# swift-nav.net
KiCad netlist of a schematic drawn in EAGLE
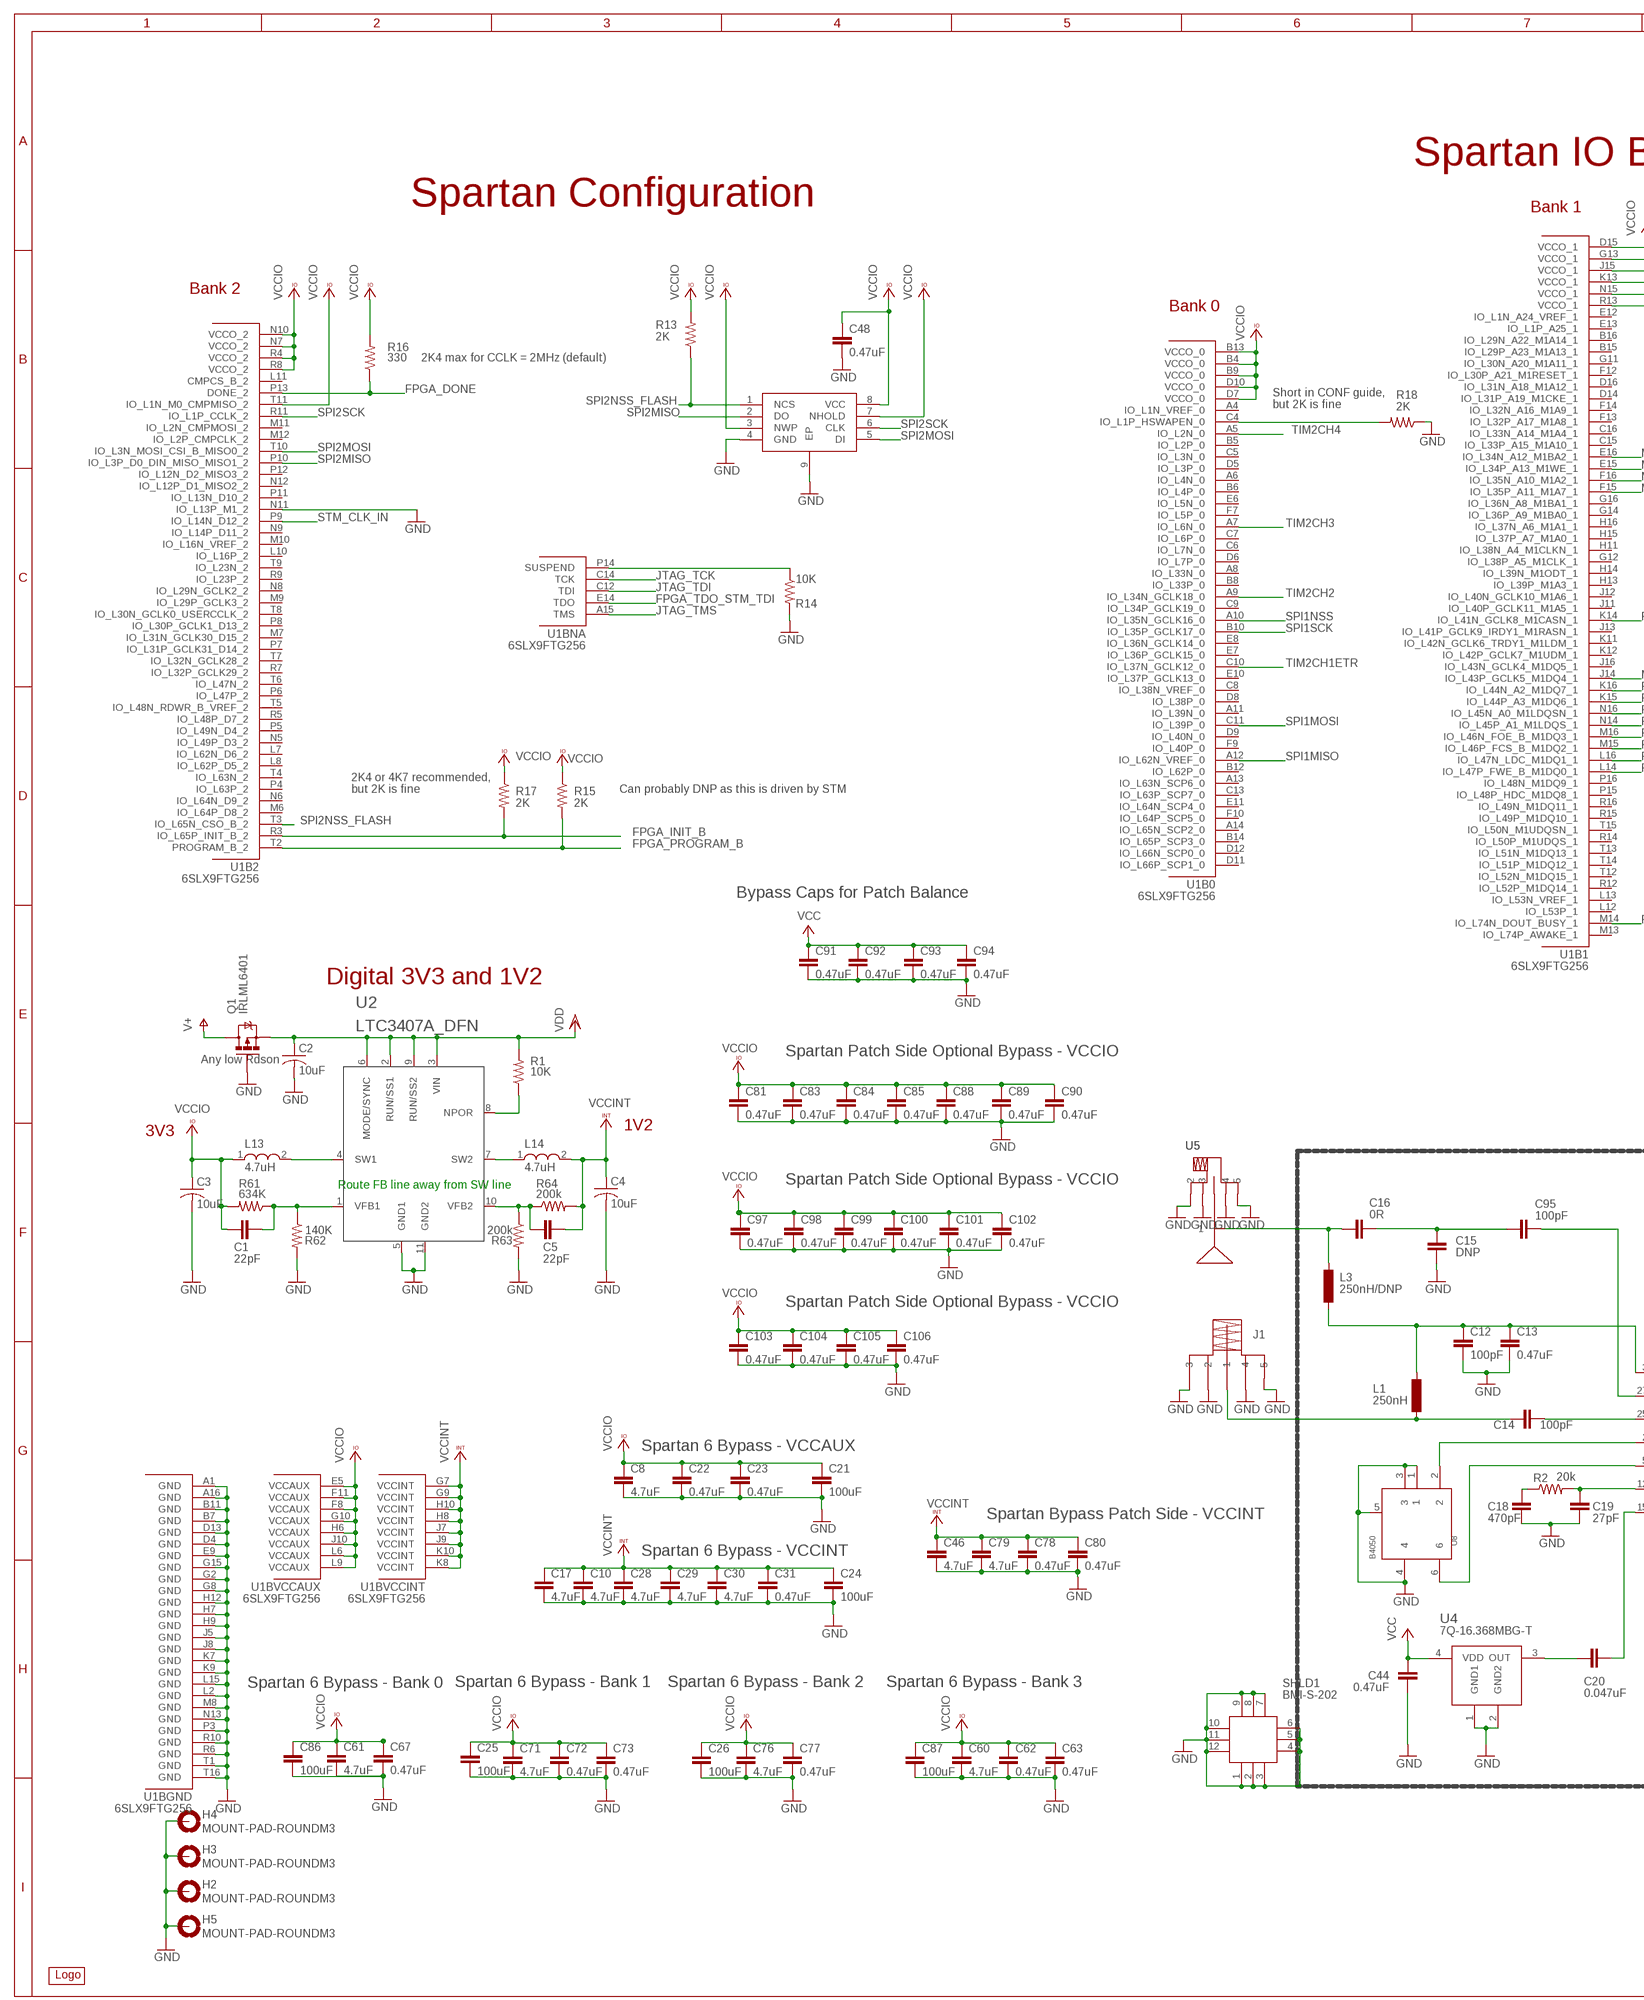
[diagram p0: schematic, sheet 1, part 1 of 2]
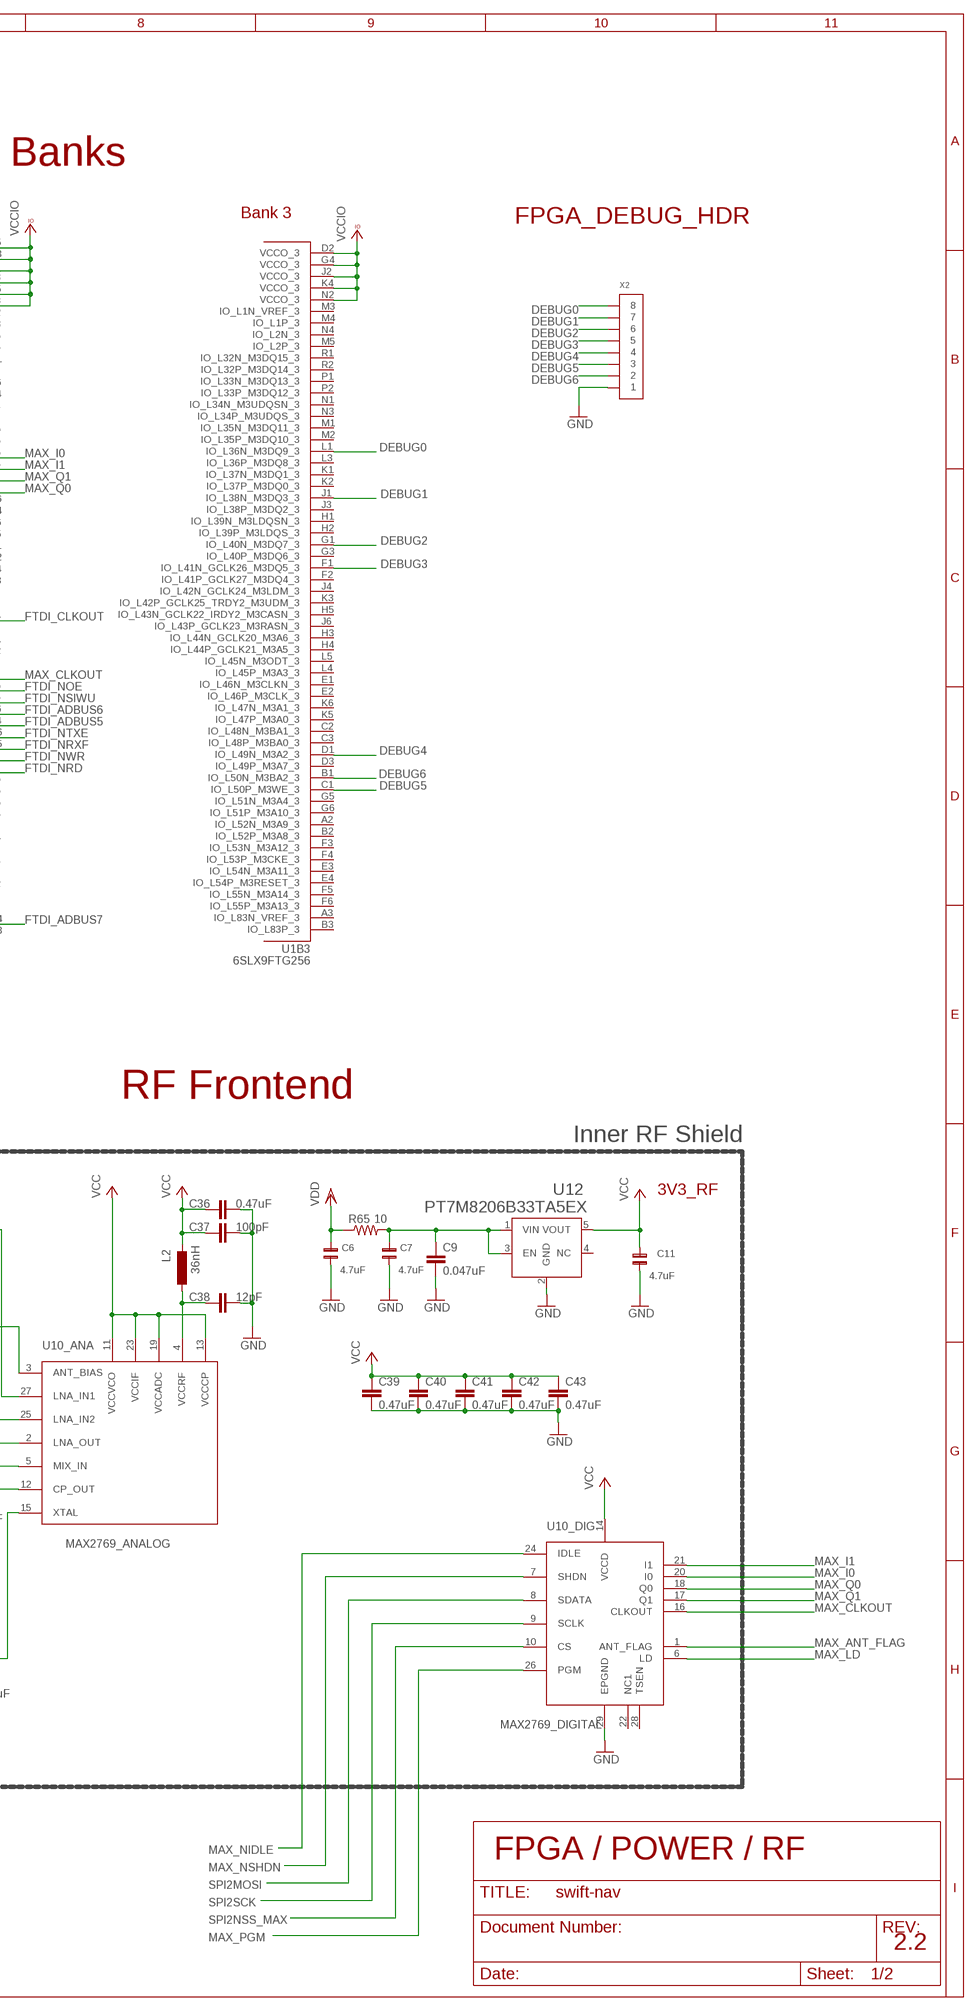
[diagram p1: schematic, sheet 1, part 2 of 2]
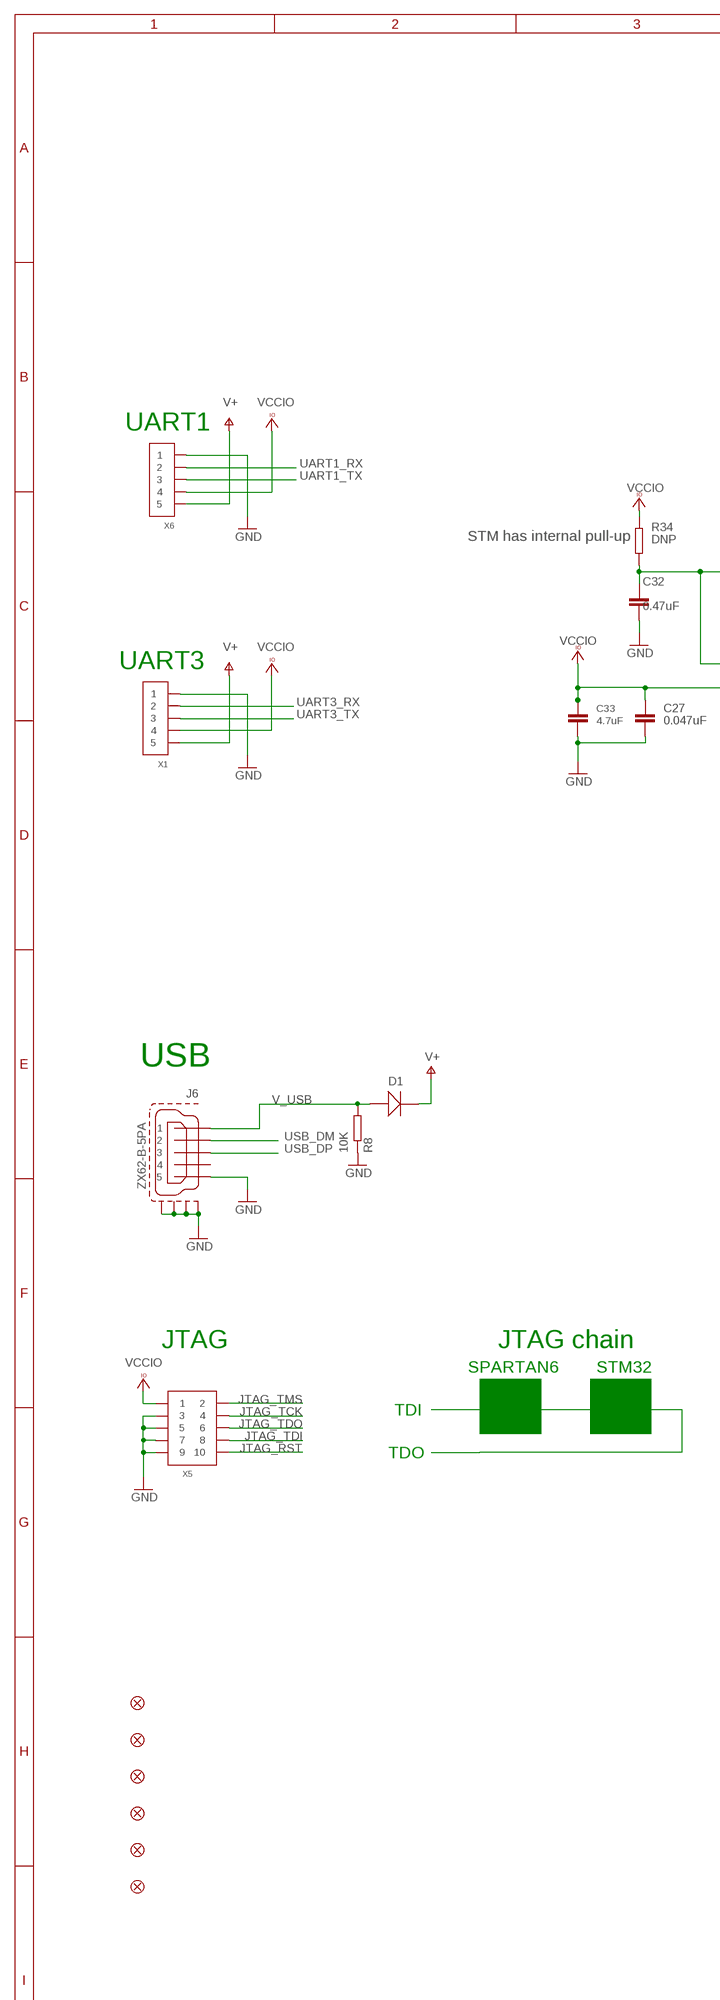
[diagram p2: schematic, sheet 2, part 1 of 2]
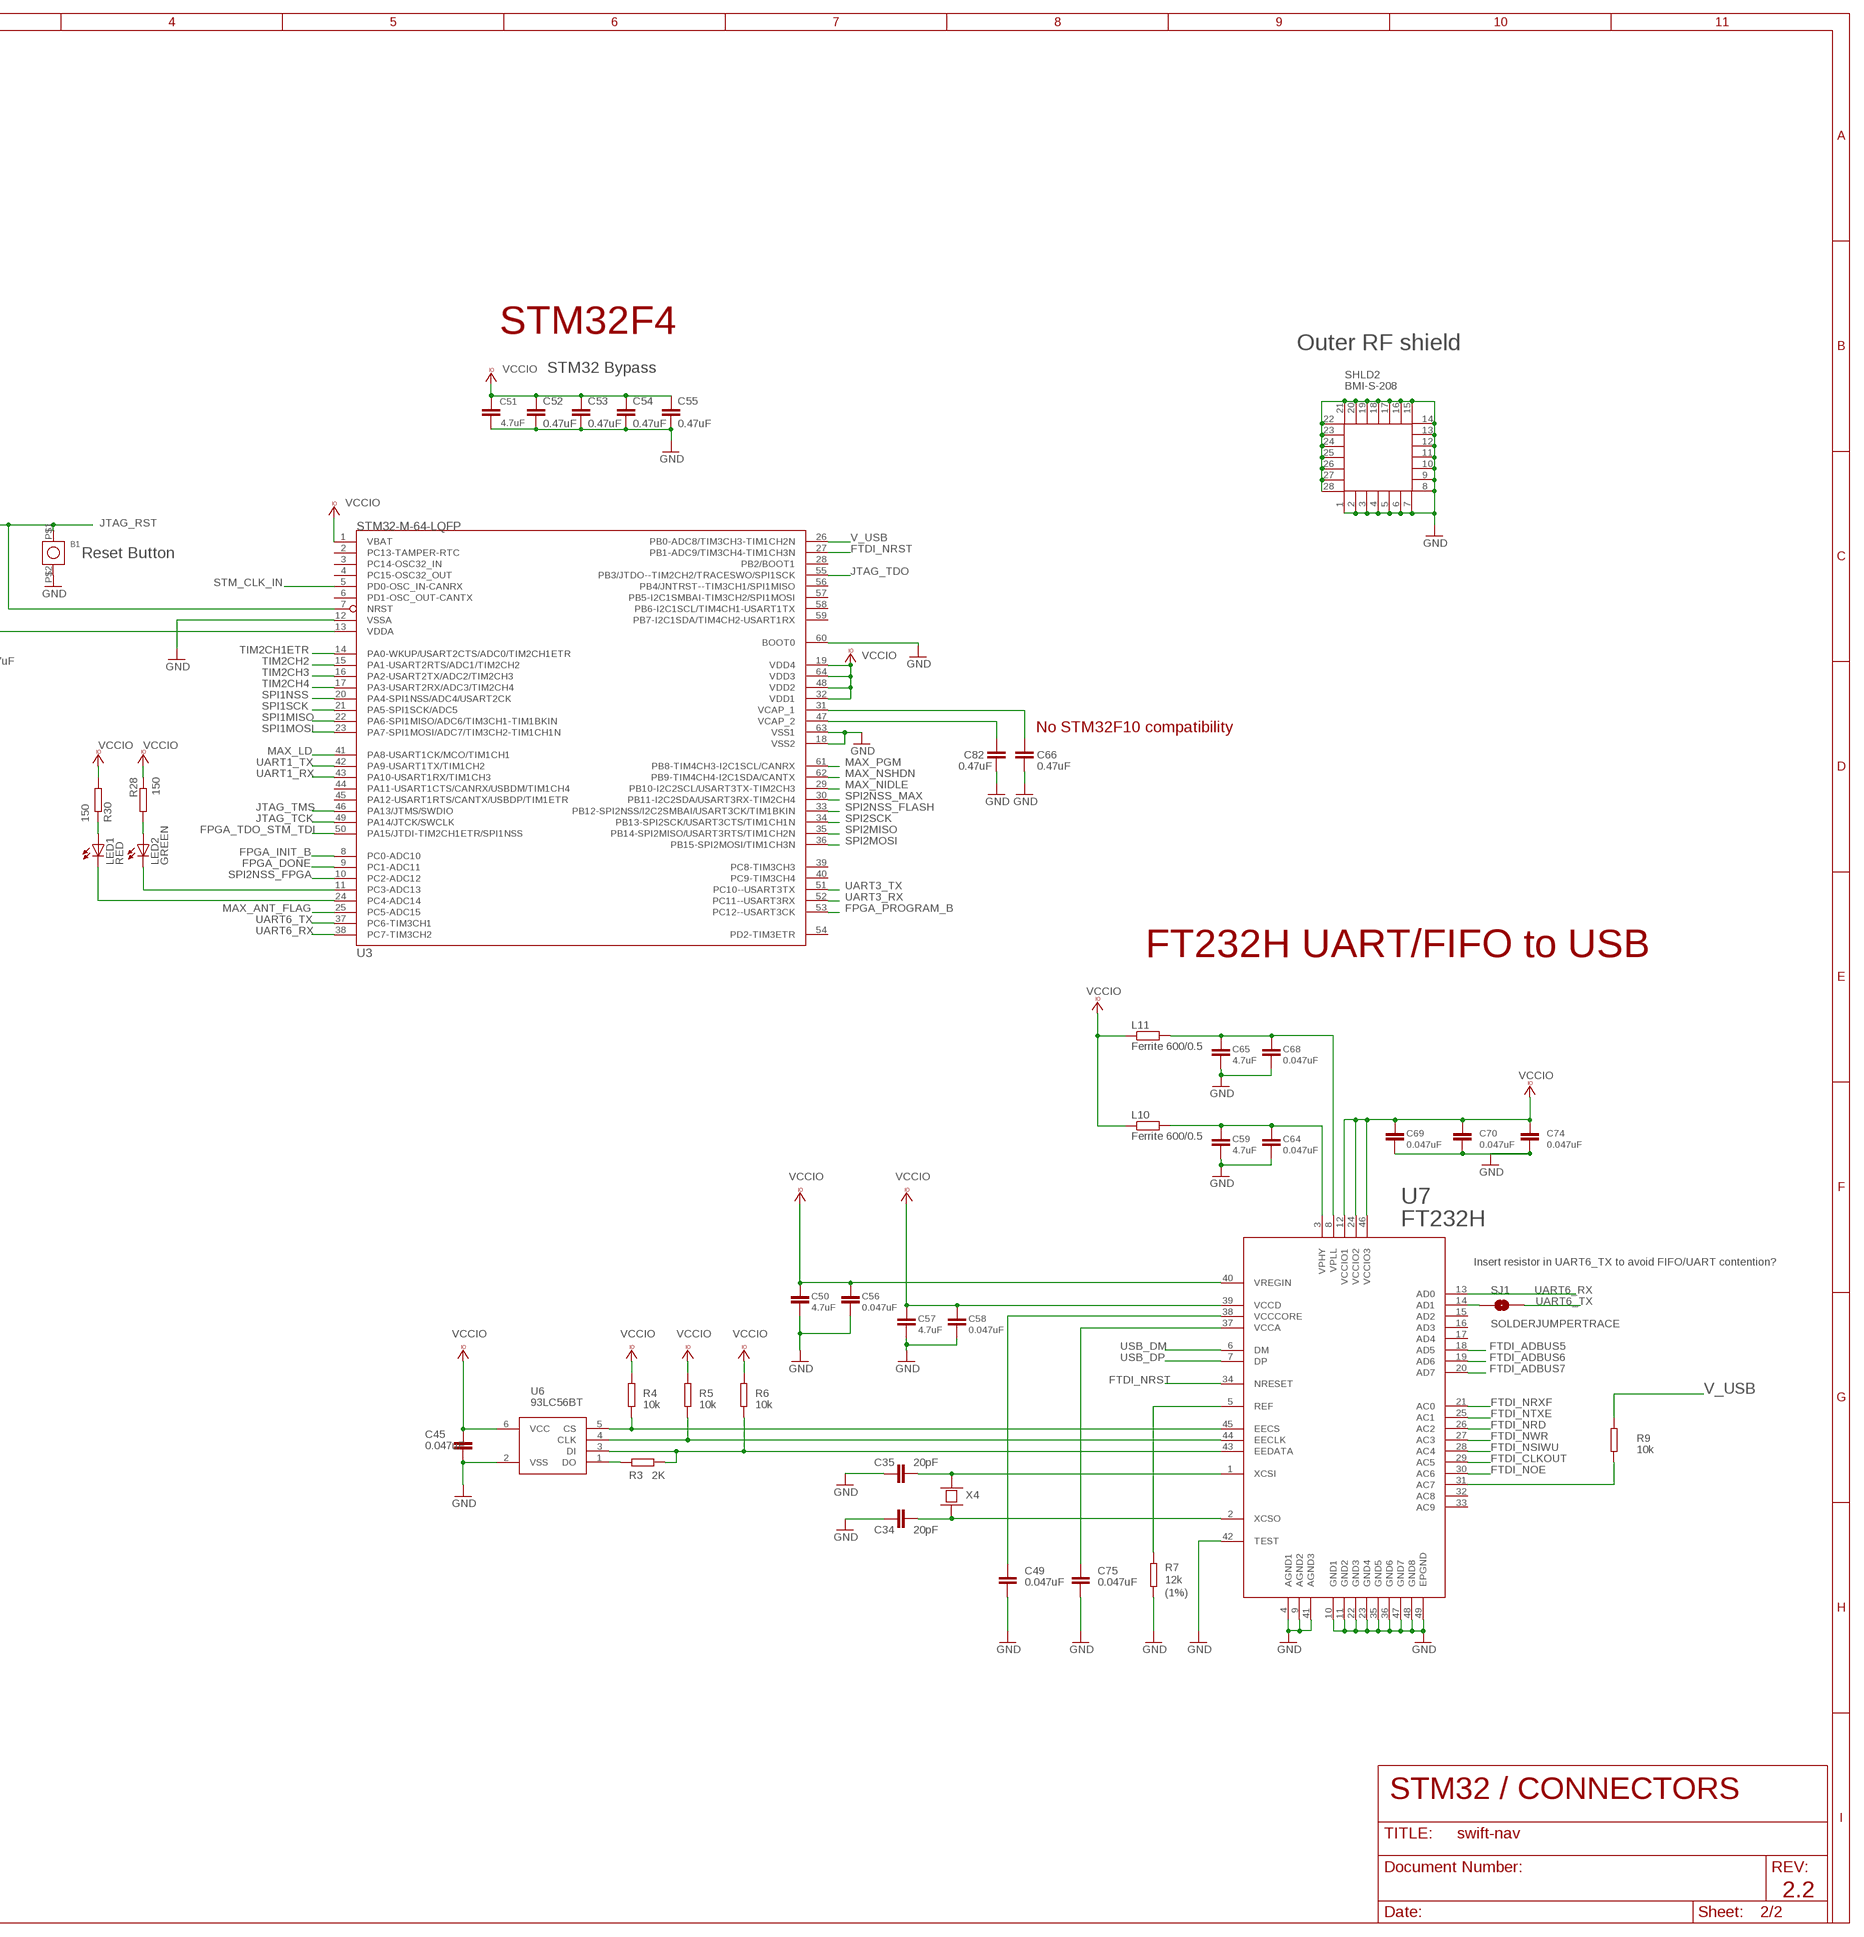
[diagram p3: schematic, sheet 2, part 2 of 2]

(export (version "E")
  (design (tool "Eeschema 10.0.6"))
  (components
    (comp (ref "C1")
      (value "22pF")
      (footprint "eagle-import:C0402")
      (libsource (lib "eagle-import") (part "C-EUC0402"))
    )
    (comp (ref "C2")
      (value "10uF")
      (footprint "eagle-import:C1206")
      (libsource (lib "eagle-import") (part "C-USC1206"))
    )
    (comp (ref "C3")
      (value "10uF")
      (footprint "eagle-import:C1206")
      (libsource (lib "eagle-import") (part "C-USC1206"))
    )
    (comp (ref "C4")
      (value "10uF")
      (footprint "eagle-import:C1206")
      (libsource (lib "eagle-import") (part "C-USC1206"))
    )
    (comp (ref "C5")
      (value "22pF")
      (footprint "eagle-import:C0402")
      (libsource (lib "eagle-import") (part "C-EUC0402"))
    )
    (comp (ref "C6")
      (value "4.7uF")
      (footprint "eagle-import:0603")
      (libsource (lib "eagle-import") (part "C0603"))
    )
    (comp (ref "C7")
      (value "4.7uF")
      (footprint "eagle-import:0603")
      (libsource (lib "eagle-import") (part "C0603"))
    )
    (comp (ref "C8")
      (value "4.7uF")
      (footprint "eagle-import:C0603K")
      (libsource (lib "eagle-import") (part "C-EUC0603K"))
    )
    (comp (ref "C9")
      (value "0.047uF")
      (footprint "eagle-import:C0402")
      (libsource (lib "eagle-import") (part "C-EUC0402"))
    )
    (comp (ref "C10")
      (value "4.7uF")
      (footprint "eagle-import:C0603K")
      (libsource (lib "eagle-import") (part "C-EUC0603K"))
    )
    (comp (ref "C11")
      (value "4.7uF")
      (footprint "eagle-import:0603")
      (libsource (lib "eagle-import") (part "C0603"))
    )
    (comp (ref "C12")
      (value "100pF")
      (footprint "eagle-import:C0402")
      (libsource (lib "eagle-import") (part "C-EUC0402"))
    )
    (comp (ref "C13")
      (value "0.47uF")
      (footprint "eagle-import:C0402")
      (libsource (lib "eagle-import") (part "C-EUC0402"))
    )
    (comp (ref "C14")
      (value "100pF")
      (footprint "eagle-import:C0402")
      (libsource (lib "eagle-import") (part "C-EUC0402"))
    )
    (comp (ref "C15")
      (value "DNP")
      (footprint "eagle-import:C0402")
      (libsource (lib "eagle-import") (part "C-EUC0402"))
    )
    (comp (ref "C16")
      (value "0R")
      (footprint "eagle-import:C0402")
      (libsource (lib "eagle-import") (part "C-EUC0402"))
    )
    (comp (ref "C17")
      (value "4.7uF")
      (footprint "eagle-import:C0603K")
      (libsource (lib "eagle-import") (part "C-EUC0603K"))
    )
    (comp (ref "C18")
      (value "470pF")
      (footprint "eagle-import:C0402")
      (libsource (lib "eagle-import") (part "C-EUC0402"))
    )
    (comp (ref "C19")
      (value "27pF")
      (footprint "eagle-import:C0402")
      (libsource (lib "eagle-import") (part "C-EUC0402"))
    )
    (comp (ref "C20")
      (value "0.047uF")
      (footprint "eagle-import:C0402")
      (libsource (lib "eagle-import") (part "C-EUC0402"))
    )
    (comp (ref "C21")
      (value "100uF")
      (footprint "eagle-import:C1210K")
      (libsource (lib "eagle-import") (part "C-EUC1210K"))
    )
    (comp (ref "C22")
      (value "0.47uF")
      (footprint "eagle-import:C0402")
      (libsource (lib "eagle-import") (part "C-EUC0402"))
    )
    (comp (ref "C23")
      (value "0.47uF")
      (footprint "eagle-import:C0402")
      (libsource (lib "eagle-import") (part "C-EUC0402"))
    )
    (comp (ref "C24")
      (value "100uF")
      (footprint "eagle-import:C1210K")
      (libsource (lib "eagle-import") (part "C-EUC1210K"))
    )
    (comp (ref "C25")
      (value "100uF")
      (footprint "eagle-import:C1210K")
      (libsource (lib "eagle-import") (part "C-EUC1210K"))
    )
    (comp (ref "C26")
      (value "100uF")
      (footprint "eagle-import:C1210K")
      (libsource (lib "eagle-import") (part "C-EUC1210K"))
    )
    (comp (ref "C28")
      (value "4.7uF")
      (footprint "eagle-import:C0603K")
      (libsource (lib "eagle-import") (part "C-EUC0603K"))
    )
    (comp (ref "C29")
      (value "4.7uF")
      (footprint "eagle-import:C0603K")
      (libsource (lib "eagle-import") (part "C-EUC0603K"))
    )
    (comp (ref "C30")
      (value "4.7uF")
      (footprint "eagle-import:C0603K")
      (libsource (lib "eagle-import") (part "C-EUC0603K"))
    )
    (comp (ref "C31")
      (value "0.47uF")
      (footprint "eagle-import:C0402")
      (libsource (lib "eagle-import") (part "C-EUC0402"))
    )
    (comp (ref "C36")
      (value "0.47uF")
      (footprint "eagle-import:C0402")
      (libsource (lib "eagle-import") (part "C-EUC0402"))
    )
    (comp (ref "C37")
      (value "100pF")
      (footprint "eagle-import:C0402")
      (libsource (lib "eagle-import") (part "C-EUC0402"))
    )
    (comp (ref "C38")
      (value "12pF")
      (footprint "eagle-import:C0402")
      (libsource (lib "eagle-import") (part "C-EUC0402"))
    )
    (comp (ref "C39")
      (value "0.47uF")
      (footprint "eagle-import:C0402")
      (libsource (lib "eagle-import") (part "C-EUC0402"))
    )
    (comp (ref "C40")
      (value "0.47uF")
      (footprint "eagle-import:C0402")
      (libsource (lib "eagle-import") (part "C-EUC0402"))
    )
    (comp (ref "C41")
      (value "0.47uF")
      (footprint "eagle-import:C0402")
      (libsource (lib "eagle-import") (part "C-EUC0402"))
    )
    (comp (ref "C42")
      (value "0.47uF")
      (footprint "eagle-import:C0402")
      (libsource (lib "eagle-import") (part "C-EUC0402"))
    )
    (comp (ref "C43")
      (value "0.47uF")
      (footprint "eagle-import:C0402")
      (libsource (lib "eagle-import") (part "C-EUC0402"))
    )
    (comp (ref "C44")
      (value "0.47uF")
      (footprint "eagle-import:C0402")
      (libsource (lib "eagle-import") (part "C-EUC0402"))
    )
    (comp (ref "C46")
      (value "4.7uF")
      (footprint "eagle-import:C0603K")
      (libsource (lib "eagle-import") (part "C-EUC0603K"))
    )
    (comp (ref "C48")
      (value "0.47uF")
      (footprint "eagle-import:C0402")
      (libsource (lib "eagle-import") (part "C-EUC0402"))
    )
    (comp (ref "C60")
      (value "4.7uF")
      (footprint "eagle-import:C0603K")
      (libsource (lib "eagle-import") (part "C-EUC0603K"))
    )
    (comp (ref "C61")
      (value "4.7uF")
      (footprint "eagle-import:C0603K")
      (libsource (lib "eagle-import") (part "C-EUC0603K"))
    )
    (comp (ref "C62")
      (value "0.47uF")
      (footprint "eagle-import:C0402")
      (libsource (lib "eagle-import") (part "C-EUC0402"))
    )
    (comp (ref "C63")
      (value "0.47uF")
      (footprint "eagle-import:C0402")
      (libsource (lib "eagle-import") (part "C-EUC0402"))
    )
    (comp (ref "C67")
      (value "0.47uF")
      (footprint "eagle-import:C0402")
      (libsource (lib "eagle-import") (part "C-EUC0402"))
    )
    (comp (ref "C71")
      (value "4.7uF")
      (footprint "eagle-import:C0603K")
      (libsource (lib "eagle-import") (part "C-EUC0603K"))
    )
    (comp (ref "C72")
      (value "0.47uF")
      (footprint "eagle-import:C0402")
      (libsource (lib "eagle-import") (part "C-EUC0402"))
    )
    (comp (ref "C73")
      (value "0.47uF")
      (footprint "eagle-import:C0402")
      (libsource (lib "eagle-import") (part "C-EUC0402"))
    )
    (comp (ref "C76")
      (value "4.7uF")
      (footprint "eagle-import:C0603K")
      (libsource (lib "eagle-import") (part "C-EUC0603K"))
    )
    (comp (ref "C77")
      (value "0.47uF")
      (footprint "eagle-import:C0402")
      (libsource (lib "eagle-import") (part "C-EUC0402"))
    )
    (comp (ref "C78")
      (value "0.47uF")
      (footprint "eagle-import:C0402")
      (libsource (lib "eagle-import") (part "C-EUC0402"))
    )
    (comp (ref "C79")
      (value "4.7uF")
      (footprint "eagle-import:C0603K")
      (libsource (lib "eagle-import") (part "C-EUC0603K"))
    )
    (comp (ref "C80")
      (value "0.47uF")
      (footprint "eagle-import:C0402")
      (libsource (lib "eagle-import") (part "C-EUC0402"))
    )
    (comp (ref "C81")
      (value "0.47uF")
      (footprint "eagle-import:C0402")
      (libsource (lib "eagle-import") (part "C-EUC0402"))
    )
    (comp (ref "C83")
      (value "0.47uF")
      (footprint "eagle-import:C0402")
      (libsource (lib "eagle-import") (part "C-EUC0402"))
    )
    (comp (ref "C84")
      (value "0.47uF")
      (footprint "eagle-import:C0402")
      (libsource (lib "eagle-import") (part "C-EUC0402"))
    )
    (comp (ref "C85")
      (value "0.47uF")
      (footprint "eagle-import:C0402")
      (libsource (lib "eagle-import") (part "C-EUC0402"))
    )
    (comp (ref "C86")
      (value "100uF")
      (footprint "eagle-import:C1210K")
      (libsource (lib "eagle-import") (part "C-EUC1210K"))
    )
    (comp (ref "C87")
      (value "100uF")
      (footprint "eagle-import:C1210K")
      (libsource (lib "eagle-import") (part "C-EUC1210K"))
    )
    (comp (ref "C88")
      (value "0.47uF")
      (footprint "eagle-import:C0402")
      (libsource (lib "eagle-import") (part "C-EUC0402"))
    )
    (comp (ref "C89")
      (value "0.47uF")
      (footprint "eagle-import:C0402")
      (libsource (lib "eagle-import") (part "C-EUC0402"))
    )
    (comp (ref "C90")
      (value "0.47uF")
      (footprint "eagle-import:C0402")
      (libsource (lib "eagle-import") (part "C-EUC0402"))
    )
    (comp (ref "C91")
      (value "0.47uF")
      (footprint "eagle-import:C0402")
      (libsource (lib "eagle-import") (part "C-EUC0402"))
    )
    (comp (ref "C92")
      (value "0.47uF")
      (footprint "eagle-import:C0402")
      (libsource (lib "eagle-import") (part "C-EUC0402"))
    )
    (comp (ref "C93")
      (value "0.47uF")
      (footprint "eagle-import:C0402")
      (libsource (lib "eagle-import") (part "C-EUC0402"))
    )
    (comp (ref "C94")
      (value "0.47uF")
      (footprint "eagle-import:C0402")
      (libsource (lib "eagle-import") (part "C-EUC0402"))
    )
    (comp (ref "C95")
      (value "100pF")
      (footprint "eagle-import:C0402")
      (libsource (lib "eagle-import") (part "C-EUC0402"))
    )
    (comp (ref "C97")
      (value "0.47uF")
      (footprint "eagle-import:C0402")
      (libsource (lib "eagle-import") (part "C-EUC0402"))
    )
    (comp (ref "C98")
      (value "0.47uF")
      (footprint "eagle-import:C0402")
      (libsource (lib "eagle-import") (part "C-EUC0402"))
    )
    (comp (ref "C99")
      (value "0.47uF")
      (footprint "eagle-import:C0402")
      (libsource (lib "eagle-import") (part "C-EUC0402"))
    )
    (comp (ref "C100")
      (value "0.47uF")
      (footprint "eagle-import:C0402")
      (libsource (lib "eagle-import") (part "C-EUC0402"))
    )
    (comp (ref "C101")
      (value "0.47uF")
      (footprint "eagle-import:C0402")
      (libsource (lib "eagle-import") (part "C-EUC0402"))
    )
    (comp (ref "C102")
      (value "0.47uF")
      (footprint "eagle-import:C0402")
      (libsource (lib "eagle-import") (part "C-EUC0402"))
    )
    (comp (ref "C103")
      (value "0.47uF")
      (footprint "eagle-import:C0402")
      (libsource (lib "eagle-import") (part "C-EUC0402"))
    )
    (comp (ref "C104")
      (value "0.47uF")
      (footprint "eagle-import:C0402")
      (libsource (lib "eagle-import") (part "C-EUC0402"))
    )
    (comp (ref "C105")
      (value "0.47uF")
      (footprint "eagle-import:C0402")
      (libsource (lib "eagle-import") (part "C-EUC0402"))
    )
    (comp (ref "C106")
      (value "0.47uF")
      (footprint "eagle-import:C0402")
      (libsource (lib "eagle-import") (part "C-EUC0402"))
    )
    (comp (ref "H2")
      (value "MOUNT-PAD-ROUNDM3")
      (footprint "eagle-import:M3-PAD")
      (libsource (lib "eagle-import") (part "MOUNT-PAD-ROUNDM3"))
    )
    (comp (ref "H3")
      (value "MOUNT-PAD-ROUNDM3")
      (footprint "eagle-import:M3-PAD")
      (libsource (lib "eagle-import") (part "MOUNT-PAD-ROUNDM3"))
    )
    (comp (ref "H4")
      (value "MOUNT-PAD-ROUNDM3")
      (footprint "eagle-import:M3-PAD")
      (libsource (lib "eagle-import") (part "MOUNT-PAD-ROUNDM3"))
    )
    (comp (ref "H5")
      (value "MOUNT-PAD-ROUNDM3")
      (footprint "eagle-import:M3-PAD")
      (libsource (lib "eagle-import") (part "MOUNT-PAD-ROUNDM3"))
    )
    (comp (ref "J1")
      (value "SMA_EDGE")
      (footprint "eagle-import:SMA_EDGE")
      (libsource (lib "eagle-import") (part "SMA_EDGE"))
    )
    (comp (ref "L1")
      (value "250nH")
      (footprint "eagle-import:0402-IND")
      (libsource (lib "eagle-import") (part "INDUCTOR-0402"))
    )
    (comp (ref "L2")
      (value "36nH")
      (footprint "eagle-import:0402-IND")
      (libsource (lib "eagle-import") (part "INDUCTOR-0402"))
    )
    (comp (ref "L3")
      (value "250nH/DNP")
      (footprint "eagle-import:0402-IND")
      (libsource (lib "eagle-import") (part "INDUCTOR-0402"))
    )
    (comp (ref "L13")
      (value "4.7uH")
      (footprint "eagle-import:LQM2HPN4R7MG0L")
      (libsource (lib "eagle-import") (part "LQM2HPN4R7MG0L"))
    )
    (comp (ref "L14")
      (value "4.7uH")
      (footprint "eagle-import:LQM2HPN4R7MG0L")
      (libsource (lib "eagle-import") (part "LQM2HPN4R7MG0L"))
    )
    (comp (ref "Q1")
      (value "IRLML6401")
      (footprint "eagle-import:SOT23-3")
      (libsource (lib "eagle-import") (part "MOSFET-PCHANNELSMD"))
    )
    (comp (ref "R1")
      (value "10K")
      (footprint "eagle-import:R0402")
      (libsource (lib "eagle-import") (part "R-US_R0402"))
    )
    (comp (ref "R2")
      (value "20k")
      (footprint "eagle-import:R0402")
      (libsource (lib "eagle-import") (part "R-US_R0402"))
    )
    (comp (ref "R13")
      (value "2K")
      (footprint "eagle-import:R0402")
      (libsource (lib "eagle-import") (part "R-US_R0402"))
    )
    (comp (ref "R14")
      (value "10K")
      (footprint "eagle-import:R0402")
      (libsource (lib "eagle-import") (part "R-US_R0402"))
    )
    (comp (ref "R15")
      (value "2K")
      (footprint "eagle-import:R0402")
      (libsource (lib "eagle-import") (part "R-US_R0402"))
    )
    (comp (ref "R16")
      (value "330")
      (footprint "eagle-import:R0402")
      (libsource (lib "eagle-import") (part "R-US_R0402"))
    )
    (comp (ref "R17")
      (value "2K")
      (footprint "eagle-import:R0402")
      (libsource (lib "eagle-import") (part "R-US_R0402"))
    )
    (comp (ref "R18")
      (value "2K")
      (footprint "eagle-import:R0402")
      (libsource (lib "eagle-import") (part "R-US_R0402"))
    )
    (comp (ref "R61")
      (value "634K")
      (footprint "eagle-import:R0402")
      (libsource (lib "eagle-import") (part "R-US_R0402"))
    )
    (comp (ref "R62")
      (value "140K")
      (footprint "eagle-import:R0402")
      (libsource (lib "eagle-import") (part "R-US_R0402"))
    )
    (comp (ref "R63")
      (value "200k")
      (footprint "eagle-import:R0402")
      (libsource (lib "eagle-import") (part "R-US_R0402"))
    )
    (comp (ref "R64")
      (value "200k")
      (footprint "eagle-import:R0402")
      (libsource (lib "eagle-import") (part "R-US_R0402"))
    )
    (comp (ref "R65")
      (value "10")
      (footprint "eagle-import:R0402")
      (libsource (lib "eagle-import") (part "R-US_R0402"))
    )
    (comp (ref "SHLD1")
      (value "BMI-S-202")
      (footprint "eagle-import:BMI-S-202")
      (libsource (lib "eagle-import") (part "BMI-S-202"))
    )
    (comp (ref "U$1")
      (value "LOGOINITIALS")
      (footprint "eagle-import:INITIALS")
      (libsource (lib "eagle-import") (part "LOGOINITIALS"))
    )
    (comp (ref "U1")
      (value "6SLX9FTG256")
      (footprint "eagle-import:FT256")
      (libsource (lib "eagle-import") (part "6SLX9FTG256"))
    )
    (comp (ref "U2")
      (value "LTC3407A_DFN")
      (footprint "eagle-import:DFN10")
      (libsource (lib "eagle-import") (part "LTC3407A_DFN"))
    )
    (comp (ref "U4")
      (value "7Q-16.368MBG-T")
      (footprint "eagle-import:TCX_7Q")
      (libsource (lib "eagle-import") (part "7Q-16.368MBG-T"))
    )
    (comp (ref "U5")
      (value "SMA_PATCH")
      (footprint "eagle-import:SMA_PATCH")
      (libsource (lib "eagle-import") (part "SMA_PATCH"))
    )
    (comp (ref "U8")
      (value "B4050")
      (footprint "eagle-import:B4050")
      (libsource (lib "eagle-import") (part "B4050"))
    )
    (comp (ref "U10")
      (value "MAX2769")
      (footprint "eagle-import:MAX2769")
      (libsource (lib "eagle-import") (part "MAX2769"))
    )
    (comp (ref "U12")
      (value "PT7M8206B33TA5EX")
      (footprint "eagle-import:PT7M8206B33TA5EX")
      (libsource (lib "eagle-import") (part "PT7M8206B33TA5EX"))
    )
    (comp (ref "U13")
      (value "M25PX80")
      (footprint "eagle-import:M25P80_MLP8")
      (libsource (lib "eagle-import") (part "M25P80_MLP8"))
    )
    (comp (ref "X2")
      (value "CONN_8-1-53261")
      (footprint "eagle-import:PB-53261-08")
      (libsource (lib "eagle-import") (part "CONN_8-1-53261"))
    )
    (comp (ref "B1")
      (value "B3U-1000P")
      (footprint "eagle-import:B3U-1000P")
      (libsource (lib "eagle-import") (part "B3U-1000P"))
    )
    (comp (ref "C27")
      (value "0.047uF")
      (footprint "eagle-import:C0402")
      (libsource (lib "eagle-import") (part "C-EUC0402"))
    )
    (comp (ref "C32")
      (value "0.47uF")
      (footprint "eagle-import:C0402")
      (libsource (lib "eagle-import") (part "C-EUC0402"))
    )
    (comp (ref "C33")
      (value "4.7uF")
      (footprint "eagle-import:C0603K")
      (libsource (lib "eagle-import") (part "C-EUC0603K"))
    )
    (comp (ref "C34")
      (value "20pF")
      (footprint "eagle-import:C0402")
      (libsource (lib "eagle-import") (part "C-EUC0402"))
    )
    (comp (ref "C35")
      (value "20pF")
      (footprint "eagle-import:C0402")
      (libsource (lib "eagle-import") (part "C-EUC0402"))
    )
    (comp (ref "C45")
      (value "0.047uF")
      (footprint "eagle-import:C0402")
      (libsource (lib "eagle-import") (part "C-EUC0402"))
    )
    (comp (ref "C49")
      (value "0.047uF")
      (footprint "eagle-import:C0402")
      (libsource (lib "eagle-import") (part "C-EUC0402"))
    )
    (comp (ref "C50")
      (value "4.7uF")
      (footprint "eagle-import:C0603K")
      (libsource (lib "eagle-import") (part "C-EUC0603K"))
    )
    (comp (ref "C51")
      (value "4.7uF")
      (footprint "eagle-import:C0603K")
      (libsource (lib "eagle-import") (part "C-EUC0603K"))
    )
    (comp (ref "C52")
      (value "0.47uF")
      (footprint "eagle-import:C0402")
      (libsource (lib "eagle-import") (part "C-EUC0402"))
    )
    (comp (ref "C53")
      (value "0.47uF")
      (footprint "eagle-import:C0402")
      (libsource (lib "eagle-import") (part "C-EUC0402"))
    )
    (comp (ref "C54")
      (value "0.47uF")
      (footprint "eagle-import:C0402")
      (libsource (lib "eagle-import") (part "C-EUC0402"))
    )
    (comp (ref "C55")
      (value "0.47uF")
      (footprint "eagle-import:C0402")
      (libsource (lib "eagle-import") (part "C-EUC0402"))
    )
    (comp (ref "C56")
      (value "0.047uF")
      (footprint "eagle-import:C0603K")
      (libsource (lib "eagle-import") (part "C-EUC0603K"))
    )
    (comp (ref "C57")
      (value "4.7uF")
      (footprint "eagle-import:C0603K")
      (libsource (lib "eagle-import") (part "C-EUC0603K"))
    )
    (comp (ref "C58")
      (value "0.047uF")
      (footprint "eagle-import:C0603K")
      (libsource (lib "eagle-import") (part "C-EUC0603K"))
    )
    (comp (ref "C59")
      (value "4.7uF")
      (footprint "eagle-import:C0603K")
      (libsource (lib "eagle-import") (part "C-EUC0603K"))
    )
    (comp (ref "C64")
      (value "0.047uF")
      (footprint "eagle-import:C0603K")
      (libsource (lib "eagle-import") (part "C-EUC0603K"))
    )
    (comp (ref "C65")
      (value "4.7uF")
      (footprint "eagle-import:C0603K")
      (libsource (lib "eagle-import") (part "C-EUC0603K"))
    )
    (comp (ref "C66")
      (value "0.47uF")
      (footprint "eagle-import:C0402")
      (libsource (lib "eagle-import") (part "C-EUC0402"))
    )
    (comp (ref "C68")
      (value "0.047uF")
      (footprint "eagle-import:C0603K")
      (libsource (lib "eagle-import") (part "C-EUC0603K"))
    )
    (comp (ref "C69")
      (value "0.047uF")
      (footprint "eagle-import:C0603")
      (libsource (lib "eagle-import") (part "C-EUC0603"))
    )
    (comp (ref "C70")
      (value "0.047uF")
      (footprint "eagle-import:C0603K")
      (libsource (lib "eagle-import") (part "C-EUC0603K"))
    )
    (comp (ref "C74")
      (value "0.047uF")
      (footprint "eagle-import:C0603K")
      (libsource (lib "eagle-import") (part "C-EUC0603K"))
    )
    (comp (ref "C75")
      (value "0.047uF")
      (footprint "eagle-import:C0402")
      (libsource (lib "eagle-import") (part "C-EUC0402"))
    )
    (comp (ref "C82")
      (value "0.47uF")
      (footprint "eagle-import:C0402")
      (libsource (lib "eagle-import") (part "C-EUC0402"))
    )
    (comp (ref "D1")
      (value "MBR0520")
      (footprint "eagle-import:SOD-123")
      (libsource (lib "eagle-import") (part "MBR0520"))
    )
    (comp (ref "J6")
      (value "ZX62-B-5PA")
      (footprint "eagle-import:ZX62-B-5PA")
      (libsource (lib "eagle-import") (part "ZX62-B-5PA"))
    )
    (comp (ref "JP5")
      (value "FIDUCIAL1.5X3")
      (footprint "eagle-import:FIDUCIAL-1.5X3")
      (libsource (lib "eagle-import") (part "FIDUCIAL1.5X3"))
    )
    (comp (ref "JP6")
      (value "FIDUCIAL1.5X3")
      (footprint "eagle-import:FIDUCIAL-1.5X3")
      (libsource (lib "eagle-import") (part "FIDUCIAL1.5X3"))
    )
    (comp (ref "JP7")
      (value "FIDUCIAL1.5X3")
      (footprint "eagle-import:FIDUCIAL-1.5X3")
      (libsource (lib "eagle-import") (part "FIDUCIAL1.5X3"))
    )
    (comp (ref "JP8")
      (value "FIDUCIAL1.5X3")
      (footprint "eagle-import:FIDUCIAL-1.5X3")
      (libsource (lib "eagle-import") (part "FIDUCIAL1.5X3"))
    )
    (comp (ref "JP9")
      (value "FIDUCIAL1.5X3")
      (footprint "eagle-import:FIDUCIAL-1.5X3")
      (libsource (lib "eagle-import") (part "FIDUCIAL1.5X3"))
    )
    (comp (ref "JP10")
      (value "FIDUCIAL1.5X3")
      (footprint "eagle-import:FIDUCIAL-1.5X3")
      (libsource (lib "eagle-import") (part "FIDUCIAL1.5X3"))
    )
    (comp (ref "L10")
      (value "Ferrite 600/0.5")
      (footprint "eagle-import:R0805")
      (libsource (lib "eagle-import") (part "R-EU_R0805"))
    )
    (comp (ref "L11")
      (value "Ferrite 600/0.5")
      (footprint "eagle-import:R0805")
      (libsource (lib "eagle-import") (part "R-EU_R0805"))
    )
    (comp (ref "LED1")
      (value "RED")
      (footprint "eagle-import:CHIP-LED0603")
      (libsource (lib "eagle-import") (part "LEDCHIP-LED0603"))
    )
    (comp (ref "LED2")
      (value "GREEN")
      (footprint "eagle-import:CHIP-LED0603")
      (libsource (lib "eagle-import") (part "LEDCHIP-LED0603"))
    )
    (comp (ref "R3")
      (value "2K")
      (footprint "eagle-import:0402-RES")
      (libsource (lib "eagle-import") (part "RESISTOR-0402"))
    )
    (comp (ref "R4")
      (value "10k")
      (footprint "eagle-import:0402-RES")
      (libsource (lib "eagle-import") (part "RESISTOR-0402"))
    )
    (comp (ref "R5")
      (value "10k")
      (footprint "eagle-import:0402-RES")
      (libsource (lib "eagle-import") (part "RESISTOR-0402"))
    )
    (comp (ref "R6")
      (value "10k")
      (footprint "eagle-import:0402-RES")
      (libsource (lib "eagle-import") (part "RESISTOR-0402"))
    )
    (comp (ref "R7")
      (value "12k")
      (footprint "eagle-import:0402-RES")
      (libsource (lib "eagle-import") (part "RESISTOR-0402"))
    )
    (comp (ref "R8")
      (value "10K")
      (footprint "eagle-import:0402-RES")
      (libsource (lib "eagle-import") (part "RESISTOR-0402"))
    )
    (comp (ref "R9")
      (value "10k")
      (footprint "eagle-import:0402-RES")
      (libsource (lib "eagle-import") (part "RESISTOR-0402"))
    )
    (comp (ref "R28")
      (value "150")
      (footprint "eagle-import:0402-RES")
      (libsource (lib "eagle-import") (part "RESISTOR-0402"))
    )
    (comp (ref "R30")
      (value "150")
      (footprint "eagle-import:0402-RES")
      (libsource (lib "eagle-import") (part "RESISTOR-0402"))
    )
    (comp (ref "R34")
      (value "DNP")
      (footprint "eagle-import:0402-RES")
      (libsource (lib "eagle-import") (part "RESISTOR-0402"))
    )
    (comp (ref "SHLD2")
      (value "BMI-S-208")
      (footprint "eagle-import:BMI-S-208")
      (libsource (lib "eagle-import") (part "BMI-S-208"))
    )
    (comp (ref "SJ1")
      (value "SOLDERJUMPERTRACE")
      (footprint "eagle-import:SJ_2S-TRACE")
      (libsource (lib "eagle-import") (part "SOLDERJUMPERTRACE"))
    )
    (comp (ref "U3")
      (value "STM32-M-64-LQFP")
      (footprint "eagle-import:LQFP64")
      (libsource (lib "eagle-import") (part "STM32-M-64-LQFP"))
    )
    (comp (ref "U6")
      (value "93LC56BT-I/OT")
      (footprint "eagle-import:93AA56BT-I_OT")
      (libsource (lib "eagle-import") (part "93LC56BT-I/OT"))
    )
    (comp (ref "U7")
      (value "FT232HQ")
      (footprint "eagle-import:FT232HQ")
      (libsource (lib "eagle-import") (part "FT232HQ"))
    )
    (comp (ref "X1")
      (value "CONN_5-1-53261")
      (footprint "eagle-import:PB-53261-05")
      (libsource (lib "eagle-import") (part "CONN_5-1-53261"))
    )
    (comp (ref "X4")
      (value "NX5032GA-12M")
      (footprint "eagle-import:NX5032GA")
      (libsource (lib "eagle-import") (part "NX5032GA-12M"))
    )
    (comp (ref "X5")
      (value "CONN_5-2")
      (footprint "eagle-import:FTSH-105-D")
      (libsource (lib "eagle-import") (part "CONN_5-2"))
    )
    (comp (ref "X6")
      (value "CONN_5-1-53261")
      (footprint "eagle-import:PB-53261-05")
      (libsource (lib "eagle-import") (part "CONN_5-1-53261"))
    )
  )
  (nets
    (net (code "1") (name "DEBUG0") (class "Default")
      (node (ref "U1") (pin "L1") (pinfunction "IO_L36N_M3DQ9_3_L1") (pintype "bidirectional"))
      (node (ref "X2") (pin "8") (pinfunction "8_8") (pintype "bidirectional"))
    )
    (net (code "2") (name "DEBUG1") (class "Default")
      (node (ref "U1") (pin "J1") (pinfunction "IO_L38N_M3DQ3_3_J1") (pintype "bidirectional"))
      (node (ref "X2") (pin "7") (pinfunction "7_7") (pintype "bidirectional"))
    )
    (net (code "3") (name "DEBUG2") (class "Default")
      (node (ref "U1") (pin "G1") (pinfunction "IO_L40N_M3DQ7_3_G1") (pintype "bidirectional"))
      (node (ref "X2") (pin "6") (pinfunction "6_6") (pintype "bidirectional"))
    )
    (net (code "4") (name "DEBUG3") (class "Default")
      (node (ref "U1") (pin "F1") (pinfunction "IO_L41N_GCLK26_M3DQ5_3_F1") (pintype "bidirectional"))
      (node (ref "X2") (pin "5") (pinfunction "5_5") (pintype "bidirectional"))
    )
    (net (code "5") (name "DEBUG4") (class "Default")
      (node (ref "U1") (pin "D1") (pinfunction "IO_L49N_M3A2_3_D1") (pintype "bidirectional"))
      (node (ref "X2") (pin "4") (pinfunction "4_4") (pintype "bidirectional"))
    )
    (net (code "6") (name "DEBUG5") (class "Default")
      (node (ref "U1") (pin "C1") (pinfunction "IO_L50P_M3WE_3_C1") (pintype "bidirectional"))
      (node (ref "X2") (pin "3") (pinfunction "3_3") (pintype "bidirectional"))
    )
    (net (code "7") (name "DEBUG6") (class "Default")
      (node (ref "U1") (pin "B1") (pinfunction "IO_L50N_M3BA2_3_B1") (pintype "bidirectional"))
      (node (ref "X2") (pin "2") (pinfunction "2_2") (pintype "bidirectional"))
    )
    (net (code "8") (name "FPGA_DONE") (class "Default")
      (node (ref "R16") (pin "1") (pinfunction "1_1") (pintype "passive"))
      (node (ref "U1") (pin "P13") (pinfunction "DONE_2_P13") (pintype "bidirectional"))
      (node (ref "U3") (pin "9") (pinfunction "PC1-ADC11_9") (pintype "bidirectional"))
    )
    (net (code "9") (name "FPGA_INIT_B") (class "Default")
      (node (ref "R17") (pin "2") (pinfunction "2_2") (pintype "passive"))
      (node (ref "U1") (pin "R3") (pinfunction "IO_L65P_INIT_B_2_R3") (pintype "bidirectional"))
      (node (ref "U3") (pin "8") (pinfunction "PC0-ADC10_8") (pintype "bidirectional"))
    )
    (net (code "10") (name "FPGA_PROGRAM_B") (class "Default")
      (node (ref "R15") (pin "2") (pinfunction "2_2") (pintype "passive"))
      (node (ref "U1") (pin "T2") (pinfunction "PROGRAM_B_2_T2") (pintype "input"))
      (node (ref "U3") (pin "53") (pinfunction "PC12--USART3CK_53") (pintype "bidirectional"))
    )
    (net (code "11") (name "FPGA_TDO_STM_TDI") (class "Default")
      (node (ref "U1") (pin "E14") (pinfunction "TDO_E14") (pintype "output"))
      (node (ref "U3") (pin "50") (pinfunction "PA15/JTDI-TIM2CH1ETR/SPI1NSS_50") (pintype "bidirectional"))
    )
    (net (code "12") (name "FTDI_ADBUS5") (class "Default")
      (node (ref "U1") (pin "N14") (pinfunction "IO_L45P_A1_M1LDQS_1_N14") (pintype "bidirectional"))
      (node (ref "U7") (pin "18") (pinfunction "AD5_18") (pintype "bidirectional"))
    )
    (net (code "13") (name "FTDI_ADBUS6") (class "Default")
      (node (ref "U1") (pin "N16") (pinfunction "IO_L45N_A0_M1LDQSN_1_N16") (pintype "bidirectional"))
      (node (ref "U7") (pin "19") (pinfunction "AD6_19") (pintype "bidirectional"))
    )
    (net (code "14") (name "FTDI_ADBUS7") (class "Default")
      (node (ref "U1") (pin "M14") (pinfunction "IO_L74N_DOUT_BUSY_1_M14") (pintype "bidirectional"))
      (node (ref "U7") (pin "20") (pinfunction "AD7_20") (pintype "bidirectional"))
    )
    (net (code "15") (name "FTDI_CLKOUT") (class "Default")
      (node (ref "U1") (pin "K14") (pinfunction "IO_L41N_GCLK8_M1CASN_1_K14") (pintype "bidirectional"))
      (node (ref "U7") (pin "29") (pinfunction "AC5_29") (pintype "bidirectional"))
    )
    (net (code "16") (name "FTDI_NOE") (class "Default")
      (node (ref "U1") (pin "K16") (pinfunction "IO_L44N_A2_M1DQ7_1_K16") (pintype "bidirectional"))
      (node (ref "U7") (pin "30") (pinfunction "AC6_30") (pintype "bidirectional"))
    )
    (net (code "17") (name "FTDI_NRD") (class "Default")
      (node (ref "U1") (pin "L14") (pinfunction "IO_L47P_FWE_B_M1DQ0_1_L14") (pintype "bidirectional"))
      (node (ref "U7") (pin "26") (pinfunction "AC2_26") (pintype "bidirectional"))
    )
    (net (code "18") (name "FTDI_NRST") (class "Default")
      (node (ref "U3") (pin "27") (pinfunction "PB1-ADC9/TIM3CH4-TIM1CH3N_27") (pintype "bidirectional"))
      (node (ref "U7") (pin "34") (pinfunction "NRESET_34") (pintype "input"))
    )
    (net (code "19") (name "FTDI_NRXF") (class "Default")
      (node (ref "U1") (pin "M15") (pinfunction "IO_L46P_FCS_B_M1DQ2_1_M15") (pintype "bidirectional"))
      (node (ref "U7") (pin "21") (pinfunction "AC0_21") (pintype "bidirectional"))
    )
    (net (code "20") (name "FTDI_NSIWU") (class "Default")
      (node (ref "U1") (pin "K15") (pinfunction "IO_L44P_A3_M1DQ6_1_K15") (pintype "bidirectional"))
      (node (ref "U7") (pin "28") (pinfunction "AC4_28") (pintype "bidirectional"))
    )
    (net (code "21") (name "FTDI_NTXE") (class "Default")
      (node (ref "U1") (pin "M16") (pinfunction "IO_L46N_FOE_B_M1DQ3_1_M16") (pintype "bidirectional"))
      (node (ref "U7") (pin "25") (pinfunction "AC1_25") (pintype "bidirectional"))
    )
    (net (code "22") (name "FTDI_NWR") (class "Default")
      (node (ref "U1") (pin "L16") (pinfunction "IO_L47N_LDC_M1DQ1_1_L16") (pintype "bidirectional"))
      (node (ref "U7") (pin "27") (pinfunction "AC3_27") (pintype "bidirectional"))
    )
    (net (code "23") (name "GND") (class "Default")
      (node (ref "B1") (pin "P$2") (pinfunction "2_P$2") (pintype "bidirectional"))
      (node (ref "C10") (pin "2") (pinfunction "2_2") (pintype "passive"))
      (node (ref "C100") (pin "2") (pinfunction "2_2") (pintype "passive"))
      (node (ref "C101") (pin "2") (pinfunction "2_2") (pintype "passive"))
      (node (ref "C102") (pin "2") (pinfunction "2_2") (pintype "passive"))
      (node (ref "C103") (pin "2") (pinfunction "2_2") (pintype "passive"))
      (node (ref "C104") (pin "2") (pinfunction "2_2") (pintype "passive"))
      (node (ref "C105") (pin "2") (pinfunction "2_2") (pintype "passive"))
      (node (ref "C106") (pin "2") (pinfunction "2_2") (pintype "passive"))
      (node (ref "C11") (pin "1") (pinfunction "1_1") (pintype "passive"))
      (node (ref "C12") (pin "2") (pinfunction "2_2") (pintype "passive"))
      (node (ref "C13") (pin "2") (pinfunction "2_2") (pintype "passive"))
      (node (ref "C15") (pin "1") (pinfunction "1_1") (pintype "passive"))
      (node (ref "C17") (pin "2") (pinfunction "2_2") (pintype "passive"))
      (node (ref "C18") (pin "2") (pinfunction "2_2") (pintype "passive"))
      (node (ref "C19") (pin "2") (pinfunction "2_2") (pintype "passive"))
      (node (ref "C2") (pin "2") (pinfunction "2_2") (pintype "passive"))
      (node (ref "C21") (pin "2") (pinfunction "2_2") (pintype "passive"))
      (node (ref "C22") (pin "2") (pinfunction "2_2") (pintype "passive"))
      (node (ref "C23") (pin "2") (pinfunction "2_2") (pintype "passive"))
      (node (ref "C24") (pin "2") (pinfunction "2_2") (pintype "passive"))
      (node (ref "C25") (pin "2") (pinfunction "2_2") (pintype "passive"))
      (node (ref "C26") (pin "2") (pinfunction "2_2") (pintype "passive"))
      (node (ref "C27") (pin "2") (pinfunction "2_2") (pintype "passive"))
      (node (ref "C28") (pin "2") (pinfunction "2_2") (pintype "passive"))
      (node (ref "C29") (pin "2") (pinfunction "2_2") (pintype "passive"))
      (node (ref "C3") (pin "2") (pinfunction "2_2") (pintype "passive"))
      (node (ref "C30") (pin "2") (pinfunction "2_2") (pintype "passive"))
      (node (ref "C31") (pin "2") (pinfunction "2_2") (pintype "passive"))
      (node (ref "C32") (pin "2") (pinfunction "2_2") (pintype "passive"))
      (node (ref "C33") (pin "1") (pinfunction "1_1") (pintype "passive"))
      (node (ref "C34") (pin "2") (pinfunction "2_2") (pintype "passive"))
      (node (ref "C35") (pin "2") (pinfunction "2_2") (pintype "passive"))
      (node (ref "C36") (pin "2") (pinfunction "2_2") (pintype "passive"))
      (node (ref "C37") (pin "2") (pinfunction "2_2") (pintype "passive"))
      (node (ref "C38") (pin "2") (pinfunction "2_2") (pintype "passive"))
      (node (ref "C39") (pin "2") (pinfunction "2_2") (pintype "passive"))
      (node (ref "C4") (pin "2") (pinfunction "2_2") (pintype "passive"))
      (node (ref "C40") (pin "2") (pinfunction "2_2") (pintype "passive"))
      (node (ref "C41") (pin "2") (pinfunction "2_2") (pintype "passive"))
      (node (ref "C42") (pin "2") (pinfunction "2_2") (pintype "passive"))
      (node (ref "C43") (pin "2") (pinfunction "2_2") (pintype "passive"))
      (node (ref "C44") (pin "2") (pinfunction "2_2") (pintype "passive"))
      (node (ref "C45") (pin "2") (pinfunction "2_2") (pintype "passive"))
      (node (ref "C46") (pin "2") (pinfunction "2_2") (pintype "passive"))
      (node (ref "C48") (pin "2") (pinfunction "2_2") (pintype "passive"))
      (node (ref "C49") (pin "2") (pinfunction "2_2") (pintype "passive"))
      (node (ref "C50") (pin "1") (pinfunction "1_1") (pintype "passive"))
      (node (ref "C51") (pin "1") (pinfunction "1_1") (pintype "passive"))
      (node (ref "C52") (pin "2") (pinfunction "2_2") (pintype "passive"))
      (node (ref "C53") (pin "2") (pinfunction "2_2") (pintype "passive"))
      (node (ref "C54") (pin "2") (pinfunction "2_2") (pintype "passive"))
      (node (ref "C55") (pin "2") (pinfunction "2_2") (pintype "passive"))
      (node (ref "C56") (pin "2") (pinfunction "2_2") (pintype "passive"))
      (node (ref "C57") (pin "1") (pinfunction "1_1") (pintype "passive"))
      (node (ref "C58") (pin "2") (pinfunction "2_2") (pintype "passive"))
      (node (ref "C59") (pin "1") (pinfunction "1_1") (pintype "passive"))
      (node (ref "C6") (pin "1") (pinfunction "1_1") (pintype "passive"))
      (node (ref "C60") (pin "2") (pinfunction "2_2") (pintype "passive"))
      (node (ref "C61") (pin "2") (pinfunction "2_2") (pintype "passive"))
      (node (ref "C62") (pin "2") (pinfunction "2_2") (pintype "passive"))
      (node (ref "C63") (pin "2") (pinfunction "2_2") (pintype "passive"))
      (node (ref "C64") (pin "2") (pinfunction "2_2") (pintype "passive"))
      (node (ref "C65") (pin "1") (pinfunction "1_1") (pintype "passive"))
      (node (ref "C66") (pin "2") (pinfunction "2_2") (pintype "passive"))
      (node (ref "C67") (pin "2") (pinfunction "2_2") (pintype "passive"))
      (node (ref "C68") (pin "2") (pinfunction "2_2") (pintype "passive"))
      (node (ref "C69") (pin "2") (pinfunction "2_2") (pintype "passive"))
      (node (ref "C7") (pin "1") (pinfunction "1_1") (pintype "passive"))
      (node (ref "C70") (pin "2") (pinfunction "2_2") (pintype "passive"))
      (node (ref "C71") (pin "2") (pinfunction "2_2") (pintype "passive"))
      (node (ref "C72") (pin "2") (pinfunction "2_2") (pintype "passive"))
      (node (ref "C73") (pin "2") (pinfunction "2_2") (pintype "passive"))
      (node (ref "C74") (pin "2") (pinfunction "2_2") (pintype "passive"))
      (node (ref "C75") (pin "2") (pinfunction "2_2") (pintype "passive"))
      (node (ref "C76") (pin "2") (pinfunction "2_2") (pintype "passive"))
      (node (ref "C77") (pin "2") (pinfunction "2_2") (pintype "passive"))
      (node (ref "C78") (pin "2") (pinfunction "2_2") (pintype "passive"))
      (node (ref "C79") (pin "2") (pinfunction "2_2") (pintype "passive"))
      (node (ref "C8") (pin "2") (pinfunction "2_2") (pintype "passive"))
      (node (ref "C80") (pin "2") (pinfunction "2_2") (pintype "passive"))
      (node (ref "C81") (pin "2") (pinfunction "2_2") (pintype "passive"))
      (node (ref "C82") (pin "1") (pinfunction "1_1") (pintype "passive"))
      (node (ref "C83") (pin "2") (pinfunction "2_2") (pintype "passive"))
      (node (ref "C84") (pin "2") (pinfunction "2_2") (pintype "passive"))
      (node (ref "C85") (pin "2") (pinfunction "2_2") (pintype "passive"))
      (node (ref "C86") (pin "2") (pinfunction "2_2") (pintype "passive"))
      (node (ref "C87") (pin "2") (pinfunction "2_2") (pintype "passive"))
      (node (ref "C88") (pin "2") (pinfunction "2_2") (pintype "passive"))
      (node (ref "C89") (pin "2") (pinfunction "2_2") (pintype "passive"))
      (node (ref "C9") (pin "2") (pinfunction "2_2") (pintype "passive"))
      (node (ref "C90") (pin "2") (pinfunction "2_2") (pintype "passive"))
      (node (ref "C91") (pin "2") (pinfunction "2_2") (pintype "passive"))
      (node (ref "C92") (pin "2") (pinfunction "2_2") (pintype "passive"))
      (node (ref "C93") (pin "2") (pinfunction "2_2") (pintype "passive"))
      (node (ref "C94") (pin "2") (pinfunction "2_2") (pintype "passive"))
      (node (ref "C97") (pin "2") (pinfunction "2_2") (pintype "passive"))
      (node (ref "C98") (pin "2") (pinfunction "2_2") (pintype "passive"))
      (node (ref "C99") (pin "2") (pinfunction "2_2") (pintype "passive"))
      (node (ref "H2") (pin "B3,0") (pinfunction "MOUNT_B3,0") (pintype "passive"))
      (node (ref "H3") (pin "B3,0") (pinfunction "MOUNT_B3,0") (pintype "passive"))
      (node (ref "H4") (pin "B3,0") (pinfunction "MOUNT_B3,0") (pintype "passive"))
      (node (ref "H5") (pin "B3,0") (pinfunction "MOUNT_B3,0") (pintype "passive"))
      (node (ref "J1") (pin "P2") (pinfunction "2_P2") (pintype "power_in"))
      (node (ref "J1") (pin "P3") (pinfunction "3_P3") (pintype "power_in"))
      (node (ref "J1") (pin "P4") (pinfunction "4_P4") (pintype "power_in"))
      (node (ref "J1") (pin "P5") (pinfunction "5_P5") (pintype "power_in"))
      (node (ref "J6") (pin "GND_LEFT") (pinfunction "S1_GND_LEFT") (pintype "passive"))
      (node (ref "J6") (pin "GND_RIGHT") (pinfunction "S2_GND_RIGHT") (pintype "passive"))
      (node (ref "J6") (pin "GND_UP_LEFT") (pinfunction "S3_GND_UP_LEFT") (pintype "passive"))
      (node (ref "J6") (pin "GND_UP_RIGHT") (pinfunction "S4_GND_UP_RIGHT") (pintype "passive"))
      (node (ref "J6") (pin "PIN_5") (pinfunction "5_PIN_5") (pintype "input"))
      (node (ref "Q1") (pin "1") (pinfunction "G_1") (pintype "passive"))
      (node (ref "R14") (pin "2") (pinfunction "2_2") (pintype "passive"))
      (node (ref "R18") (pin "1") (pinfunction "1_1") (pintype "passive"))
      (node (ref "R62") (pin "2") (pinfunction "2_2") (pintype "passive"))
      (node (ref "R63") (pin "2") (pinfunction "2_2") (pintype "passive"))
      (node (ref "R7") (pin "P$2") (pinfunction "2_P$2") (pintype "passive"))
      (node (ref "R8") (pin "P$1") (pinfunction "1_P$1") (pintype "passive"))
      (node (ref "SHLD1") (pin "1") (pinfunction "P$1_1") (pintype "power_in"))
      (node (ref "SHLD1") (pin "10") (pinfunction "P$10_10") (pintype "power_in"))
      (node (ref "SHLD1") (pin "11") (pinfunction "P$11_11") (pintype "power_in"))
      (node (ref "SHLD1") (pin "12") (pinfunction "P$12_12") (pintype "power_in"))
      (node (ref "SHLD1") (pin "2") (pinfunction "P$2_2") (pintype "power_in"))
      (node (ref "SHLD1") (pin "3") (pinfunction "P$3_3") (pintype "power_in"))
      (node (ref "SHLD1") (pin "4") (pinfunction "P$4_4") (pintype "power_in"))
      (node (ref "SHLD1") (pin "5") (pinfunction "P$5_5") (pintype "power_in"))
      (node (ref "SHLD1") (pin "6") (pinfunction "P$6_6") (pintype "power_in"))
      (node (ref "SHLD1") (pin "7") (pinfunction "P$7_7") (pintype "power_in"))
      (node (ref "SHLD1") (pin "8") (pinfunction "P$8_8") (pintype "power_in"))
      (node (ref "SHLD1") (pin "9") (pinfunction "P$9_9") (pintype "power_in"))
      (node (ref "SHLD2") (pin "1") (pinfunction "P$1_1") (pintype "power_in"))
      (node (ref "SHLD2") (pin "10") (pinfunction "P$10_10") (pintype "power_in"))
      (node (ref "SHLD2") (pin "11") (pinfunction "P$11_11") (pintype "power_in"))
      (node (ref "SHLD2") (pin "12") (pinfunction "P$12_12") (pintype "power_in"))
      (node (ref "SHLD2") (pin "13") (pinfunction "P$13_13") (pintype "power_in"))
      (node (ref "SHLD2") (pin "14") (pinfunction "P$14_14") (pintype "power_in"))
      (node (ref "SHLD2") (pin "15") (pinfunction "P$15_15") (pintype "power_in"))
      (node (ref "SHLD2") (pin "16") (pinfunction "P$16_16") (pintype "power_in"))
      (node (ref "SHLD2") (pin "17") (pinfunction "P$17_17") (pintype "power_in"))
      (node (ref "SHLD2") (pin "18") (pinfunction "P$18_18") (pintype "power_in"))
      (node (ref "SHLD2") (pin "19") (pinfunction "P$19_19") (pintype "power_in"))
      (node (ref "SHLD2") (pin "2") (pinfunction "P$2_2") (pintype "power_in"))
      (node (ref "SHLD2") (pin "20") (pinfunction "P$20_20") (pintype "power_in"))
      (node (ref "SHLD2") (pin "21") (pinfunction "P$21_21") (pintype "power_in"))
      (node (ref "SHLD2") (pin "22") (pinfunction "P$22_22") (pintype "power_in"))
      (node (ref "SHLD2") (pin "23") (pinfunction "P$23_23") (pintype "power_in"))
      (node (ref "SHLD2") (pin "24") (pinfunction "P$24_24") (pintype "power_in"))
      (node (ref "SHLD2") (pin "25") (pinfunction "P$25_25") (pintype "power_in"))
      (node (ref "SHLD2") (pin "26") (pinfunction "P$26_26") (pintype "power_in"))
      (node (ref "SHLD2") (pin "27") (pinfunction "P$27_27") (pintype "power_in"))
      (node (ref "SHLD2") (pin "28") (pinfunction "P$28_28") (pintype "power_in"))
      (node (ref "SHLD2") (pin "3") (pinfunction "P$3_3") (pintype "power_in"))
      (node (ref "SHLD2") (pin "4") (pinfunction "P$4_4") (pintype "power_in"))
      (node (ref "SHLD2") (pin "5") (pinfunction "P$5_5") (pintype "power_in"))
      (node (ref "SHLD2") (pin "6") (pinfunction "P$6_6") (pintype "power_in"))
      (node (ref "SHLD2") (pin "7") (pinfunction "P$7_7") (pintype "power_in"))
      (node (ref "SHLD2") (pin "8") (pinfunction "P$8_8") (pintype "power_in"))
      (node (ref "SHLD2") (pin "9") (pinfunction "P$9_9") (pintype "power_in"))
      (node (ref "U1") (pin "A1") (pinfunction "GND_A1") (pintype "power_in"))
      (node (ref "U1") (pin "A16") (pinfunction "GND_A16") (pintype "power_in"))
      (node (ref "U1") (pin "B11") (pinfunction "GND_B11") (pintype "power_in"))
      (node (ref "U1") (pin "B7") (pinfunction "GND_B7") (pintype "power_in"))
      (node (ref "U1") (pin "D13") (pinfunction "GND_D13") (pintype "power_in"))
      (node (ref "U1") (pin "D4") (pinfunction "GND_D4") (pintype "power_in"))
      (node (ref "U1") (pin "E9") (pinfunction "GND_E9") (pintype "power_in"))
      (node (ref "U1") (pin "G15") (pinfunction "GND_G15") (pintype "power_in"))
      (node (ref "U1") (pin "G2") (pinfunction "GND_G2") (pintype "power_in"))
      (node (ref "U1") (pin "G8") (pinfunction "GND_G8") (pintype "power_in"))
      (node (ref "U1") (pin "H12") (pinfunction "GND_H12") (pintype "power_in"))
      (node (ref "U1") (pin "H7") (pinfunction "GND_H7") (pintype "power_in"))
      (node (ref "U1") (pin "H9") (pinfunction "GND_H9") (pintype "power_in"))
      (node (ref "U1") (pin "J5") (pinfunction "GND_J5") (pintype "power_in"))
      (node (ref "U1") (pin "J8") (pinfunction "GND_J8") (pintype "power_in"))
      (node (ref "U1") (pin "K7") (pinfunction "GND_K7") (pintype "power_in"))
      (node (ref "U1") (pin "K9") (pinfunction "GND_K9") (pintype "power_in"))
      (node (ref "U1") (pin "L15") (pinfunction "GND_L15") (pintype "power_in"))
      (node (ref "U1") (pin "L2") (pinfunction "GND_L2") (pintype "power_in"))
      (node (ref "U1") (pin "M8") (pinfunction "GND_M8") (pintype "power_in"))
      (node (ref "U1") (pin "N11") (pinfunction "IO_L13P_M1_2_N11") (pintype "bidirectional"))
      (node (ref "U1") (pin "N13") (pinfunction "GND_N13") (pintype "power_in"))
      (node (ref "U1") (pin "P3") (pinfunction "GND_P3") (pintype "power_in"))
      (node (ref "U1") (pin "R10") (pinfunction "GND_R10") (pintype "power_in"))
      (node (ref "U1") (pin "R6") (pinfunction "GND_R6") (pintype "power_in"))
      (node (ref "U1") (pin "T1") (pinfunction "GND_T1") (pintype "power_in"))
      (node (ref "U1") (pin "T16") (pinfunction "GND_T16") (pintype "power_in"))
      (node (ref "U10") (pin "29") (pinfunction "EPGND_29") (pintype "bidirectional"))
      (node (ref "U12") (pin "2") (pinfunction "GND_2") (pintype "bidirectional"))
      (node (ref "U13") (pin "4") (pinfunction "GND_4") (pintype "power_in"))
      (node (ref "U13") (pin "9") (pinfunction "EP_9") (pintype "power_in"))
      (node (ref "U2") (pin "11") (pinfunction "GND2_11") (pintype "bidirectional"))
      (node (ref "U2") (pin "5") (pinfunction "GND1_5") (pintype "bidirectional"))
      (node (ref "U3") (pin "12") (pinfunction "VSSA_12") (pintype "power_in"))
      (node (ref "U3") (pin "18") (pinfunction "VSS2_18") (pintype "bidirectional"))
      (node (ref "U3") (pin "60") (pinfunction "BOOT0_60") (pintype "input"))
      (node (ref "U3") (pin "63") (pinfunction "VSS1_63") (pintype "power_in"))
      (node (ref "U4") (pin "1") (pinfunction "GND1_1") (pintype "bidirectional"))
      (node (ref "U4") (pin "2") (pinfunction "GND2_2") (pintype "bidirectional"))
      (node (ref "U5") (pin "P2") (pinfunction "2_P2") (pintype "power_in"))
      (node (ref "U5") (pin "P3") (pinfunction "3_P3") (pintype "power_in"))
      (node (ref "U5") (pin "P4") (pinfunction "4_P4") (pintype "power_in"))
      (node (ref "U5") (pin "P5") (pinfunction "5_P5") (pintype "power_in"))
      (node (ref "U6") (pin "2") (pinfunction "VSS_2") (pintype "power_in"))
      (node (ref "U7") (pin "10") (pinfunction "GND1_10") (pintype "power_in"))
      (node (ref "U7") (pin "11") (pinfunction "GND2_11") (pintype "power_in"))
      (node (ref "U7") (pin "22") (pinfunction "GND3_22") (pintype "power_in"))
      (node (ref "U7") (pin "23") (pinfunction "GND4_23") (pintype "power_in"))
      (node (ref "U7") (pin "35") (pinfunction "GND5_35") (pintype "power_in"))
      (node (ref "U7") (pin "36") (pinfunction "GND6_36") (pintype "power_in"))
      (node (ref "U7") (pin "4") (pinfunction "AGND1_4") (pintype "power_in"))
      (node (ref "U7") (pin "41") (pinfunction "AGND3_41") (pintype "power_in"))
      (node (ref "U7") (pin "42") (pinfunction "TEST_42") (pintype "input"))
      (node (ref "U7") (pin "47") (pinfunction "GND7_47") (pintype "power_in"))
      (node (ref "U7") (pin "48") (pinfunction "GND8_48") (pintype "power_in"))
      (node (ref "U7") (pin "49") (pinfunction "EPGND_49") (pintype "power_in"))
      (node (ref "U7") (pin "9") (pinfunction "AGND2_9") (pintype "power_in"))
      (node (ref "U8") (pin "1") (pinfunction "1_1") (pintype "power_in"))
      (node (ref "U8") (pin "3") (pinfunction "3_3") (pintype "power_in"))
      (node (ref "U8") (pin "4") (pinfunction "4_4") (pintype "output"))
      (node (ref "U8") (pin "5") (pinfunction "5_5") (pintype "power_in"))
      (node (ref "X1") (pin "1") (pinfunction "1_1") (pintype "bidirectional"))
      (node (ref "X2") (pin "1") (pinfunction "1_1") (pintype "bidirectional"))
      (node (ref "X5") (pin "3") (pinfunction "3_3") (pintype "bidirectional"))
      (node (ref "X5") (pin "5") (pinfunction "5_5") (pintype "bidirectional"))
      (node (ref "X5") (pin "7") (pinfunction "7_7") (pintype "bidirectional"))
      (node (ref "X5") (pin "9") (pinfunction "9_9") (pintype "bidirectional"))
      (node (ref "X6") (pin "1") (pinfunction "1_1") (pintype "bidirectional"))
    )
    (net (code "24") (name "JTAG_RST") (class "Default")
      (node (ref "B1") (pin "P$1") (pinfunction "1_P$1") (pintype "bidirectional"))
      (node (ref "C32") (pin "1") (pinfunction "1_1") (pintype "passive"))
      (node (ref "R34") (pin "P$1") (pinfunction "1_P$1") (pintype "passive"))
      (node (ref "U3") (pin "7") (pinfunction "NRST_7") (pintype "bidirectional"))
      (node (ref "X5") (pin "10") (pinfunction "10_10") (pintype "bidirectional"))
    )
    (net (code "25") (name "JTAG_TCK") (class "Default")
      (node (ref "U1") (pin "C14") (pinfunction "TCK_C14") (pintype "input"))
      (node (ref "U3") (pin "49") (pinfunction "PA14/JTCK/SWCLK_49") (pintype "bidirectional"))
      (node (ref "X5") (pin "4") (pinfunction "4_4") (pintype "bidirectional"))
    )
    (net (code "26") (name "JTAG_TDI") (class "Default")
      (node (ref "U1") (pin "C12") (pinfunction "TDI_C12") (pintype "input"))
      (node (ref "X5") (pin "8") (pinfunction "8_8") (pintype "bidirectional"))
    )
    (net (code "27") (name "JTAG_TDO") (class "Default")
      (node (ref "U3") (pin "55") (pinfunction "PB3/JTDO--TIM2CH2/TRACESWO/SPI1SCK_55") (pintype "bidirectional"))
      (node (ref "X5") (pin "6") (pinfunction "6_6") (pintype "bidirectional"))
    )
    (net (code "28") (name "JTAG_TMS") (class "Default")
      (node (ref "U1") (pin "A15") (pinfunction "TMS_A15") (pintype "input"))
      (node (ref "U3") (pin "46") (pinfunction "PA13/JTMS/SWDIO_46") (pintype "bidirectional"))
      (node (ref "X5") (pin "2") (pinfunction "2_2") (pintype "bidirectional"))
    )
    (net (code "29") (name "MAX_ANT_FLAG") (class "Default")
      (node (ref "U10") (pin "1") (pinfunction "ANT_FLAG_1") (pintype "bidirectional"))
      (node (ref "U3") (pin "25") (pinfunction "PC5-ADC15_25") (pintype "bidirectional"))
    )
    (net (code "30") (name "MAX_CLKOUT") (class "Default")
      (node (ref "U1") (pin "J14") (pinfunction "IO_L43P_GCLK5_M1DQ4_1_J14") (pintype "bidirectional"))
      (node (ref "U10") (pin "16") (pinfunction "CLKOUT_16") (pintype "bidirectional"))
    )
    (net (code "31") (name "MAX_I0") (class "Default")
      (node (ref "U1") (pin "E16") (pinfunction "IO_L34N_A12_M1BA2_1_E16") (pintype "bidirectional"))
      (node (ref "U10") (pin "20") (pinfunction "I0_20") (pintype "bidirectional"))
    )
    (net (code "32") (name "MAX_I1") (class "Default")
      (node (ref "U1") (pin "E15") (pinfunction "IO_L34P_A13_M1WE_1_E15") (pintype "bidirectional"))
      (node (ref "U10") (pin "21") (pinfunction "I1_21") (pintype "bidirectional"))
    )
    (net (code "33") (name "MAX_LD") (class "Default")
      (node (ref "U10") (pin "6") (pinfunction "LD_6") (pintype "bidirectional"))
      (node (ref "U3") (pin "41") (pinfunction "PA8-USART1CK/MCO/TIM1CH1_41") (pintype "bidirectional"))
    )
    (net (code "34") (name "MAX_NIDLE") (class "Default")
      (node (ref "U10") (pin "24") (pinfunction "IDLE_24") (pintype "bidirectional"))
      (node (ref "U3") (pin "29") (pinfunction "PB10-I2C2SCL/USART3TX-TIM2CH3_29") (pintype "bidirectional"))
    )
    (net (code "35") (name "MAX_NSHDN") (class "Default")
      (node (ref "U10") (pin "7") (pinfunction "SHDN_7") (pintype "bidirectional"))
      (node (ref "U3") (pin "62") (pinfunction "PB9-TIM4CH4-I2C1SDA/CANTX_62") (pintype "bidirectional"))
    )
    (net (code "36") (name "MAX_PGM") (class "Default")
      (node (ref "U10") (pin "26") (pinfunction "PGM_26") (pintype "bidirectional"))
      (node (ref "U3") (pin "61") (pinfunction "PB8-TIM4CH3-I2C1SCL/CANRX_61") (pintype "bidirectional"))
    )
    (net (code "37") (name "MAX_Q0") (class "Default")
      (node (ref "U1") (pin "F15") (pinfunction "IO_L35P_A11_M1A7_1_F15") (pintype "bidirectional"))
      (node (ref "U10") (pin "18") (pinfunction "Q0_18") (pintype "bidirectional"))
    )
    (net (code "38") (name "MAX_Q1") (class "Default")
      (node (ref "U1") (pin "F16") (pinfunction "IO_L35N_A10_M1A2_1_F16") (pintype "bidirectional"))
      (node (ref "U10") (pin "17") (pinfunction "Q1_17") (pintype "bidirectional"))
    )
    (net (code "39") (name "Net-(C15-Pad2)") (class "Default")
      (node (ref "C15") (pin "2") (pinfunction "2_2") (pintype "passive"))
      (node (ref "C16") (pin "1") (pinfunction "1_1") (pintype "passive"))
      (node (ref "C95") (pin "1") (pinfunction "1_1") (pintype "passive"))
    )
    (net (code "40") (name "Net-(C18-Pad1)") (class "Default")
      (node (ref "C18") (pin "1") (pinfunction "1_1") (pintype "passive"))
      (node (ref "R2") (pin "1") (pinfunction "1_1") (pintype "passive"))
    )
    (net (code "41") (name "Net-(J1-1)") (class "Default")
      (node (ref "C14") (pin "1") (pinfunction "1_1") (pintype "passive"))
      (node (ref "J1") (pin "P1") (pinfunction "1_P1") (pintype "bidirectional"))
      (node (ref "L1") (pin "P$1") (pinfunction "1_P$1") (pintype "passive"))
    )
    (net (code "42") (name "Net-(L1-2)") (class "Default")
      (node (ref "C12") (pin "1") (pinfunction "1_1") (pintype "passive"))
      (node (ref "C13") (pin "1") (pinfunction "1_1") (pintype "passive"))
      (node (ref "L1") (pin "P$2") (pinfunction "2_P$2") (pintype "passive"))
      (node (ref "L3") (pin "P$1") (pinfunction "1_P$1") (pintype "passive"))
      (node (ref "U10") (pin "3") (pinfunction "ANT_BIAS_3") (pintype "bidirectional"))
    )
    (net (code "43") (name "Net-(L2-1)") (class "Default")
      (node (ref "C38") (pin "1") (pinfunction "1_1") (pintype "passive"))
      (node (ref "L2") (pin "P$1") (pinfunction "1_P$1") (pintype "passive"))
      (node (ref "U10") (pin "4") (pinfunction "VCCRF_4") (pintype "bidirectional"))
    )
    (net (code "44") (name "Net-(L3-2)") (class "Default")
      (node (ref "C16") (pin "2") (pinfunction "2_2") (pintype "passive"))
      (node (ref "L3") (pin "P$2") (pinfunction "2_P$2") (pintype "passive"))
      (node (ref "U5") (pin "P1") (pinfunction "1_P1") (pintype "bidirectional"))
    )
    (net (code "45") (name "Net-(R3-1)") (class "Default")
      (node (ref "R3") (pin "P$1") (pinfunction "1_P$1") (pintype "passive"))
      (node (ref "R6") (pin "P$2") (pinfunction "2_P$2") (pintype "passive"))
      (node (ref "U6") (pin "3") (pinfunction "DI_3") (pintype "input"))
      (node (ref "U7") (pin "43") (pinfunction "EEDATA_43") (pintype "bidirectional"))
    )
    (net (code "46") (name "Net-(R3-2)") (class "Default")
      (node (ref "R3") (pin "P$2") (pinfunction "2_P$2") (pintype "passive"))
      (node (ref "U6") (pin "1") (pinfunction "DO_1") (pintype "output"))
    )
    (net (code "47") (name "Net-(R4-2)") (class "Default")
      (node (ref "R4") (pin "P$2") (pinfunction "2_P$2") (pintype "passive"))
      (node (ref "U6") (pin "5") (pinfunction "CS_5") (pintype "input"))
      (node (ref "U7") (pin "45") (pinfunction "EECS_45") (pintype "bidirectional"))
    )
    (net (code "48") (name "Net-(R5-2)") (class "Default")
      (node (ref "R5") (pin "P$2") (pinfunction "2_P$2") (pintype "passive"))
      (node (ref "U6") (pin "4") (pinfunction "CLK_4") (pintype "input"))
      (node (ref "U7") (pin "44") (pinfunction "EECLK_44") (pintype "output"))
    )
    (net (code "49") (name "Net-(R7-1)") (class "Default")
      (node (ref "R7") (pin "P$1") (pinfunction "1_P$1") (pintype "passive"))
      (node (ref "U7") (pin "5") (pinfunction "REF_5") (pintype "input"))
    )
    (net (code "50") (name "Net-(R9-2)") (class "Default")
      (node (ref "R9") (pin "P$2") (pinfunction "2_P$2") (pintype "passive"))
      (node (ref "U7") (pin "31") (pinfunction "AC7_31") (pintype "bidirectional"))
    )
    (net (code "51") (name "Net-(R28-2)") (class "Default")
      (node (ref "LED2") (pin "A") (pinfunction "A_A") (pintype "passive"))
      (node (ref "R28") (pin "P$2") (pinfunction "2_P$2") (pintype "passive"))
    )
    (net (code "52") (name "Net-(R30-1)") (class "Default")
      (node (ref "LED1") (pin "A") (pinfunction "A_A") (pintype "passive"))
      (node (ref "R30") (pin "P$1") (pinfunction "1_P$1") (pintype "passive"))
    )
    (net (code "53") (name "Net-(U1A-IO_L1P_HSWAPEN_0)") (class "Default")
      (node (ref "R18") (pin "2") (pinfunction "2_2") (pintype "passive"))
      (node (ref "U1") (pin "C4") (pinfunction "IO_L1P_HSWAPEN_0_C4") (pintype "bidirectional"))
    )
    (net (code "54") (name "Net-(U1F-SUSPEND)") (class "Default")
      (node (ref "R14") (pin "1") (pinfunction "1_1") (pintype "passive"))
      (node (ref "U1") (pin "P14") (pinfunction "SUSPEND_P14") (pintype "input"))
    )
    (net (code "55") (name "Net-(U2-NPOR)") (class "Default")
      (node (ref "R1") (pin "1") (pinfunction "1_1") (pintype "passive"))
      (node (ref "U2") (pin "8") (pinfunction "NPOR_8") (pintype "bidirectional"))
    )
    (net (code "56") (name "Net-(U2-SW1)") (class "Default")
      (node (ref "L13") (pin "2") (pinfunction "2_2") (pintype "bidirectional"))
      (node (ref "U2") (pin "4") (pinfunction "SW1_4") (pintype "bidirectional"))
    )
    (net (code "57") (name "Net-(U2-SW2)") (class "Default")
      (node (ref "L14") (pin "1") (pinfunction "1_1") (pintype "bidirectional"))
      (node (ref "U2") (pin "7") (pinfunction "SW2_7") (pintype "bidirectional"))
    )
    (net (code "58") (name "Net-(U2-VFB1)") (class "Default")
      (node (ref "C1") (pin "1") (pinfunction "1_1") (pintype "passive"))
      (node (ref "R61") (pin "1") (pinfunction "1_1") (pintype "passive"))
      (node (ref "R62") (pin "1") (pinfunction "1_1") (pintype "passive"))
      (node (ref "U2") (pin "1") (pinfunction "VFB1_1") (pintype "bidirectional"))
    )
    (net (code "59") (name "Net-(U2-VFB2)") (class "Default")
      (node (ref "C5") (pin "2") (pinfunction "2_2") (pintype "passive"))
      (node (ref "R63") (pin "1") (pinfunction "1_1") (pintype "passive"))
      (node (ref "R64") (pin "1") (pinfunction "1_1") (pintype "passive"))
      (node (ref "U2") (pin "10") (pinfunction "VFB2_10") (pintype "bidirectional"))
    )
    (net (code "60") (name "Net-(U3-PC3-ADC13)") (class "Default")
      (node (ref "LED2") (pin "C") (pinfunction "C_C") (pintype "passive"))
      (node (ref "U3") (pin "11") (pinfunction "PC3-ADC13_11") (pintype "bidirectional"))
    )
    (net (code "61") (name "Net-(U3-PC4-ADC14)") (class "Default")
      (node (ref "LED1") (pin "C") (pinfunction "C_C") (pintype "passive"))
      (node (ref "U3") (pin "24") (pinfunction "PC4-ADC14_24") (pintype "bidirectional"))
    )
    (net (code "62") (name "Net-(U3-VCAP_1)") (class "Default")
      (node (ref "C66") (pin "1") (pinfunction "1_1") (pintype "passive"))
      (node (ref "U3") (pin "31") (pinfunction "VCAP_1_31") (pintype "power_in"))
    )
    (net (code "63") (name "Net-(U3-VCAP_2)") (class "Default")
      (node (ref "C82") (pin "2") (pinfunction "2_2") (pintype "passive"))
      (node (ref "U3") (pin "47") (pinfunction "VCAP_2_47") (pintype "power_in"))
    )
    (net (code "64") (name "Net-(U4-OUT)") (class "Default")
      (node (ref "C20") (pin "2") (pinfunction "2_2") (pintype "passive"))
      (node (ref "U4") (pin "3") (pinfunction "OUT_3") (pintype "bidirectional"))
    )
    (net (code "65") (name "Net-(U7-AD1)") (class "Default")
      (node (ref "SJ1") (pin "1") (pinfunction "1_1") (pintype "passive"))
      (node (ref "U7") (pin "14") (pinfunction "AD1_14") (pintype "bidirectional"))
    )
    (net (code "66") (name "Net-(U7-VCCA)") (class "Default")
      (node (ref "C75") (pin "1") (pinfunction "1_1") (pintype "passive"))
      (node (ref "U7") (pin "37") (pinfunction "VCCA_37") (pintype "output"))
    )
    (net (code "67") (name "Net-(U7-VCCCORE)") (class "Default")
      (node (ref "C49") (pin "1") (pinfunction "1_1") (pintype "passive"))
      (node (ref "U7") (pin "38") (pinfunction "VCCCORE_38") (pintype "output"))
    )
    (net (code "68") (name "Net-(U7-VPHY)") (class "Default")
      (node (ref "C59") (pin "2") (pinfunction "2_2") (pintype "passive"))
      (node (ref "C64") (pin "1") (pinfunction "1_1") (pintype "passive"))
      (node (ref "L10") (pin "2") (pinfunction "2_2") (pintype "passive"))
      (node (ref "U7") (pin "3") (pinfunction "VPHY_3") (pintype "power_in"))
    )
    (net (code "69") (name "Net-(U7-VPLL)") (class "Default")
      (node (ref "C65") (pin "2") (pinfunction "2_2") (pintype "passive"))
      (node (ref "C68") (pin "1") (pinfunction "1_1") (pintype "passive"))
      (node (ref "L11") (pin "2") (pinfunction "2_2") (pintype "passive"))
      (node (ref "U7") (pin "8") (pinfunction "VPLL_8") (pintype "power_in"))
    )
    (net (code "70") (name "Net-(U7-XCSI)") (class "Default")
      (node (ref "C35") (pin "1") (pinfunction "1_1") (pintype "passive"))
      (node (ref "U7") (pin "1") (pinfunction "XCSI_1") (pintype "input"))
      (node (ref "X4") (pin "1") (pinfunction "1_1") (pintype "bidirectional"))
    )
    (net (code "71") (name "Net-(U7-XCSO)") (class "Default")
      (node (ref "C34") (pin "1") (pinfunction "1_1") (pintype "passive"))
      (node (ref "U7") (pin "2") (pinfunction "XCSO_2") (pintype "output"))
      (node (ref "X4") (pin "2") (pinfunction "2_2") (pintype "bidirectional"))
    )
    (net (code "72") (name "Net-(U10A-CP_OUT)") (class "Default")
      (node (ref "C19") (pin "1") (pinfunction "1_1") (pintype "passive"))
      (node (ref "R2") (pin "2") (pinfunction "2_2") (pintype "passive"))
      (node (ref "U10") (pin "12") (pinfunction "CP_OUT_12") (pintype "bidirectional"))
    )
    (net (code "73") (name "Net-(U10A-LNA_IN1)") (class "Default")
      (node (ref "C95") (pin "2") (pinfunction "2_2") (pintype "passive"))
      (node (ref "U10") (pin "27") (pinfunction "LNA_IN1_27") (pintype "bidirectional"))
    )
    (net (code "74") (name "Net-(U10A-LNA_IN2)") (class "Default")
      (node (ref "C14") (pin "2") (pinfunction "2_2") (pintype "passive"))
      (node (ref "U10") (pin "25") (pinfunction "LNA_IN2_25") (pintype "bidirectional"))
    )
    (net (code "75") (name "Net-(U10A-LNA_OUT)") (class "Default")
      (node (ref "U10") (pin "2") (pinfunction "LNA_OUT_2") (pintype "bidirectional"))
      (node (ref "U8") (pin "2") (pinfunction "2_2") (pintype "input"))
    )
    (net (code "76") (name "Net-(U10A-MIX_IN)") (class "Default")
      (node (ref "U10") (pin "5") (pinfunction "MIX_IN_5") (pintype "bidirectional"))
      (node (ref "U8") (pin "6") (pinfunction "6_6") (pintype "output"))
    )
    (net (code "77") (name "Net-(U10A-XTAL)") (class "Default")
      (node (ref "C20") (pin "1") (pinfunction "1_1") (pintype "passive"))
      (node (ref "U10") (pin "15") (pinfunction "XTAL_15") (pintype "bidirectional"))
    )
    (net (code "78") (name "Net-(U12-EN)") (class "Default")
      (node (ref "C7") (pin "2") (pinfunction "2_2") (pintype "passive"))
      (node (ref "C9") (pin "1") (pinfunction "1_1") (pintype "passive"))
      (node (ref "R65") (pin "2") (pinfunction "2_2") (pintype "passive"))
      (node (ref "U12") (pin "1") (pinfunction "VIN_1") (pintype "bidirectional"))
      (node (ref "U12") (pin "3") (pinfunction "EN_3") (pintype "bidirectional"))
    )
    (net (code "79") (name "SPI1MISO") (class "Default")
      (node (ref "U1") (pin "A12") (pinfunction "IO_L62N_VREF_0_A12") (pintype "bidirectional"))
      (node (ref "U3") (pin "22") (pinfunction "PA6-SPI1MISO/ADC6/TIM3CH1-TIM1BKIN_22") (pintype "bidirectional"))
    )
    (net (code "80") (name "SPI1MOSI") (class "Default")
      (node (ref "U1") (pin "C11") (pinfunction "IO_L39P_0_C11") (pintype "bidirectional"))
      (node (ref "U3") (pin "23") (pinfunction "PA7-SPI1MOSI/ADC7/TIM3CH2-TIM1CH1N_23") (pintype "bidirectional"))
    )
    (net (code "81") (name "SPI1NSS") (class "Default")
      (node (ref "U1") (pin "A10") (pinfunction "IO_L35N_GCLK16_0_A10") (pintype "bidirectional"))
      (node (ref "U3") (pin "20") (pinfunction "PA4-SPI1NSS/ADC4/USART2CK_20") (pintype "bidirectional"))
    )
    (net (code "82") (name "SPI1SCK") (class "Default")
      (node (ref "U1") (pin "B10") (pinfunction "IO_L35P_GCLK17_0_B10") (pintype "bidirectional"))
      (node (ref "U3") (pin "21") (pinfunction "PA5-SPI1SCK/ADC5_21") (pintype "bidirectional"))
    )
    (net (code "83") (name "SPI2MISO") (class "Default")
      (node (ref "U1") (pin "P10") (pinfunction "IO_L3P_D0_DIN_MISO_MISO1_2_P10") (pintype "bidirectional"))
      (node (ref "U13") (pin "2") (pinfunction "DO_2") (pintype "bidirectional"))
      (node (ref "U3") (pin "35") (pinfunction "PB14-SPI2MISO/USART3RTS/TIM1CH2N_35") (pintype "bidirectional"))
    )
    (net (code "84") (name "SPI2MOSI") (class "Default")
      (node (ref "U1") (pin "T10") (pinfunction "IO_L3N_MOSI_CSI_B_MISO0_2_T10") (pintype "bidirectional"))
      (node (ref "U10") (pin "8") (pinfunction "SDATA_8") (pintype "bidirectional"))
      (node (ref "U13") (pin "5") (pinfunction "DI_5") (pintype "bidirectional"))
      (node (ref "U3") (pin "36") (pinfunction "PB15-SPI2MOSI/TIM1CH3N_36") (pintype "bidirectional"))
    )
    (net (code "85") (name "SPI2NSS_FLASH") (class "Default")
      (node (ref "R13") (pin "1") (pinfunction "1_1") (pintype "passive"))
      (node (ref "U1") (pin "T3") (pinfunction "IO_L65N_CSO_B_2_T3") (pintype "bidirectional"))
      (node (ref "U13") (pin "1") (pinfunction "NCS_1") (pintype "input"))
      (node (ref "U3") (pin "33") (pinfunction "PB12-SPI2NSS/I2C2SMBAI/USART3CK/TIM1BKIN_33") (pintype "bidirectional"))
    )
    (net (code "86") (name "SPI2NSS_FPGA") (class "Default")
      (node (ref "U3") (pin "10") (pinfunction "PC2-ADC12_10") (pintype "bidirectional"))
    )
    (net (code "87") (name "SPI2NSS_MAX") (class "Default")
      (node (ref "U10") (pin "10") (pinfunction "CS_10") (pintype "bidirectional"))
      (node (ref "U3") (pin "30") (pinfunction "PB11-I2C2SDA/USART3RX-TIM2CH4_30") (pintype "bidirectional"))
    )
    (net (code "88") (name "SPI2SCK") (class "Default")
      (node (ref "U1") (pin "R11") (pinfunction "IO_L1P_CCLK_2_R11") (pintype "bidirectional"))
      (node (ref "U10") (pin "9") (pinfunction "SCLK_9") (pintype "bidirectional"))
      (node (ref "U13") (pin "6") (pinfunction "CLK_6") (pintype "input"))
      (node (ref "U3") (pin "34") (pinfunction "PB13-SPI2SCK/USART3CTS/TIM1CH1N_34") (pintype "bidirectional"))
    )
    (net (code "89") (name "STM_CLK_IN") (class "Default")
      (node (ref "U1") (pin "P9") (pinfunction "IO_L14N_D12_2_P9") (pintype "bidirectional"))
      (node (ref "U3") (pin "5") (pinfunction "PD0-OSC_IN-CANRX_5") (pintype "input"))
    )
    (net (code "90") (name "TIM2CH1ETR") (class "Default")
      (node (ref "U1") (pin "C10") (pinfunction "IO_L37N_GCLK12_0_C10") (pintype "bidirectional"))
      (node (ref "U3") (pin "14") (pinfunction "PA0-WKUP/USART2CTS/ADC0/TIM2CH1ETR_14") (pintype "bidirectional"))
    )
    (net (code "91") (name "TIM2CH2") (class "Default")
      (node (ref "U1") (pin "A9") (pinfunction "IO_L34N_GCLK18_0_A9") (pintype "bidirectional"))
      (node (ref "U3") (pin "15") (pinfunction "PA1-USART2RTS/ADC1/TIM2CH2_15") (pintype "bidirectional"))
    )
    (net (code "92") (name "TIM2CH3") (class "Default")
      (node (ref "U1") (pin "A7") (pinfunction "IO_L6N_0_A7") (pintype "bidirectional"))
      (node (ref "U3") (pin "16") (pinfunction "PA2-USART2TX/ADC2/TIM2CH3_16") (pintype "bidirectional"))
    )
    (net (code "93") (name "TIM2CH4") (class "Default")
      (node (ref "U1") (pin "A5") (pinfunction "IO_L2N_0_A5") (pintype "bidirectional"))
      (node (ref "U3") (pin "17") (pinfunction "PA3-USART2RX/ADC3/TIM2CH4_17") (pintype "bidirectional"))
    )
    (net (code "94") (name "UART1_RX") (class "Default")
      (node (ref "U3") (pin "43") (pinfunction "PA10-USART1RX/TIM1CH3_43") (pintype "bidirectional"))
      (node (ref "X6") (pin "2") (pinfunction "2_2") (pintype "bidirectional"))
    )
    (net (code "95") (name "UART1_TX") (class "Default")
      (node (ref "U3") (pin "42") (pinfunction "PA9-USART1TX/TIM1CH2_42") (pintype "bidirectional"))
      (node (ref "X6") (pin "3") (pinfunction "3_3") (pintype "bidirectional"))
    )
    (net (code "96") (name "UART3_RX") (class "Default")
      (node (ref "U3") (pin "52") (pinfunction "PC11--USART3RX_52") (pintype "bidirectional"))
      (node (ref "X1") (pin "2") (pinfunction "2_2") (pintype "bidirectional"))
    )
    (net (code "97") (name "UART3_TX") (class "Default")
      (node (ref "U3") (pin "51") (pinfunction "PC10--USART3TX_51") (pintype "bidirectional"))
      (node (ref "X1") (pin "3") (pinfunction "3_3") (pintype "bidirectional"))
    )
    (net (code "98") (name "UART6_RX") (class "Default")
      (node (ref "U3") (pin "38") (pinfunction "PC7-TIM3CH2_38") (pintype "bidirectional"))
      (node (ref "U7") (pin "13") (pinfunction "AD0_13") (pintype "bidirectional"))
    )
    (net (code "99") (name "UART6_TX") (class "Default")
      (node (ref "SJ1") (pin "2") (pinfunction "2_2") (pintype "passive"))
      (node (ref "U3") (pin "37") (pinfunction "PC6-TIM3CH1_37") (pintype "bidirectional"))
    )
    (net (code "100") (name "USB_DM") (class "Default")
      (node (ref "J6") (pin "PIN_2") (pinfunction "2_PIN_2") (pintype "input"))
      (node (ref "U7") (pin "6") (pinfunction "DM_6") (pintype "bidirectional"))
    )
    (net (code "101") (name "USB_DP") (class "Default")
      (node (ref "J6") (pin "PIN_3") (pinfunction "3_PIN_3") (pintype "input"))
      (node (ref "U7") (pin "7") (pinfunction "DP_7") (pintype "bidirectional"))
    )
    (net (code "102") (name "V+") (class "Default")
      (node (ref "D1") (pin "2") (pinfunction "2_2") (pintype "bidirectional"))
      (node (ref "Q1") (pin "3") (pinfunction "D_3") (pintype "passive"))
      (node (ref "X1") (pin "5") (pinfunction "5_5") (pintype "bidirectional"))
      (node (ref "X6") (pin "5") (pinfunction "5_5") (pintype "bidirectional"))
    )
    (net (code "103") (name "VCC") (class "Default")
      (node (ref "C11") (pin "2") (pinfunction "2_2") (pintype "passive"))
      (node (ref "C36") (pin "1") (pinfunction "1_1") (pintype "passive"))
      (node (ref "C37") (pin "1") (pinfunction "1_1") (pintype "passive"))
      (node (ref "C39") (pin "1") (pinfunction "1_1") (pintype "passive"))
      (node (ref "C40") (pin "1") (pinfunction "1_1") (pintype "passive"))
      (node (ref "C41") (pin "1") (pinfunction "1_1") (pintype "passive"))
      (node (ref "C42") (pin "1") (pinfunction "1_1") (pintype "passive"))
      (node (ref "C43") (pin "1") (pinfunction "1_1") (pintype "passive"))
      (node (ref "C44") (pin "1") (pinfunction "1_1") (pintype "passive"))
      (node (ref "C91") (pin "1") (pinfunction "1_1") (pintype "passive"))
      (node (ref "C92") (pin "1") (pinfunction "1_1") (pintype "passive"))
      (node (ref "C93") (pin "1") (pinfunction "1_1") (pintype "passive"))
      (node (ref "C94") (pin "1") (pinfunction "1_1") (pintype "passive"))
      (node (ref "L2") (pin "P$2") (pinfunction "2_P$2") (pintype "passive"))
      (node (ref "U10") (pin "11") (pinfunction "VCCVCO_11") (pintype "bidirectional"))
      (node (ref "U10") (pin "13") (pinfunction "VCCCP_13") (pintype "bidirectional"))
      (node (ref "U10") (pin "14") (pinfunction "VCCD_14") (pintype "bidirectional"))
      (node (ref "U10") (pin "19") (pinfunction "VCCADC_19") (pintype "bidirectional"))
      (node (ref "U10") (pin "23") (pinfunction "VCCIF_23") (pintype "bidirectional"))
      (node (ref "U12") (pin "5") (pinfunction "VOUT_5") (pintype "bidirectional"))
      (node (ref "U4") (pin "4") (pinfunction "VDD_4") (pintype "bidirectional"))
    )
    (net (code "104") (name "VCCINT") (class "Default")
      (node (ref "C10") (pin "1") (pinfunction "1_1") (pintype "passive"))
      (node (ref "C17") (pin "1") (pinfunction "1_1") (pintype "passive"))
      (node (ref "C24") (pin "1") (pinfunction "1_1") (pintype "passive"))
      (node (ref "C28") (pin "1") (pinfunction "1_1") (pintype "passive"))
      (node (ref "C29") (pin "1") (pinfunction "1_1") (pintype "passive"))
      (node (ref "C30") (pin "1") (pinfunction "1_1") (pintype "passive"))
      (node (ref "C31") (pin "1") (pinfunction "1_1") (pintype "passive"))
      (node (ref "C4") (pin "1") (pinfunction "1_1") (pintype "passive"))
      (node (ref "C46") (pin "1") (pinfunction "1_1") (pintype "passive"))
      (node (ref "C5") (pin "1") (pinfunction "1_1") (pintype "passive"))
      (node (ref "C78") (pin "1") (pinfunction "1_1") (pintype "passive"))
      (node (ref "C79") (pin "1") (pinfunction "1_1") (pintype "passive"))
      (node (ref "C80") (pin "1") (pinfunction "1_1") (pintype "passive"))
      (node (ref "L14") (pin "2") (pinfunction "2_2") (pintype "bidirectional"))
      (node (ref "R64") (pin "2") (pinfunction "2_2") (pintype "passive"))
      (node (ref "U1") (pin "G7") (pinfunction "VCCINT_G7") (pintype "input"))
      (node (ref "U1") (pin "G9") (pinfunction "VCCINT_G9") (pintype "input"))
      (node (ref "U1") (pin "H10") (pinfunction "VCCINT_H10") (pintype "input"))
      (node (ref "U1") (pin "H8") (pinfunction "VCCINT_H8") (pintype "input"))
      (node (ref "U1") (pin "J7") (pinfunction "VCCINT_J7") (pintype "input"))
      (node (ref "U1") (pin "J9") (pinfunction "VCCINT_J9") (pintype "input"))
      (node (ref "U1") (pin "K10") (pinfunction "VCCINT_K10") (pintype "input"))
      (node (ref "U1") (pin "K8") (pinfunction "VCCINT_K8") (pintype "input"))
    )
    (net (code "105") (name "VCCIO") (class "Default")
      (node (ref "C1") (pin "2") (pinfunction "2_2") (pintype "passive"))
      (node (ref "C100") (pin "1") (pinfunction "1_1") (pintype "passive"))
      (node (ref "C101") (pin "1") (pinfunction "1_1") (pintype "passive"))
      (node (ref "C102") (pin "1") (pinfunction "1_1") (pintype "passive"))
      (node (ref "C103") (pin "1") (pinfunction "1_1") (pintype "passive"))
      (node (ref "C104") (pin "1") (pinfunction "1_1") (pintype "passive"))
      (node (ref "C105") (pin "1") (pinfunction "1_1") (pintype "passive"))
      (node (ref "C106") (pin "1") (pinfunction "1_1") (pintype "passive"))
      (node (ref "C21") (pin "1") (pinfunction "1_1") (pintype "passive"))
      (node (ref "C22") (pin "1") (pinfunction "1_1") (pintype "passive"))
      (node (ref "C23") (pin "1") (pinfunction "1_1") (pintype "passive"))
      (node (ref "C25") (pin "1") (pinfunction "1_1") (pintype "passive"))
      (node (ref "C26") (pin "1") (pinfunction "1_1") (pintype "passive"))
      (node (ref "C27") (pin "1") (pinfunction "1_1") (pintype "passive"))
      (node (ref "C3") (pin "1") (pinfunction "1_1") (pintype "passive"))
      (node (ref "C33") (pin "2") (pinfunction "2_2") (pintype "passive"))
      (node (ref "C45") (pin "1") (pinfunction "1_1") (pintype "passive"))
      (node (ref "C48") (pin "1") (pinfunction "1_1") (pintype "passive"))
      (node (ref "C50") (pin "2") (pinfunction "2_2") (pintype "passive"))
      (node (ref "C51") (pin "2") (pinfunction "2_2") (pintype "passive"))
      (node (ref "C52") (pin "1") (pinfunction "1_1") (pintype "passive"))
      (node (ref "C53") (pin "1") (pinfunction "1_1") (pintype "passive"))
      (node (ref "C54") (pin "1") (pinfunction "1_1") (pintype "passive"))
      (node (ref "C55") (pin "1") (pinfunction "1_1") (pintype "passive"))
      (node (ref "C56") (pin "1") (pinfunction "1_1") (pintype "passive"))
      (node (ref "C57") (pin "2") (pinfunction "2_2") (pintype "passive"))
      (node (ref "C58") (pin "1") (pinfunction "1_1") (pintype "passive"))
      (node (ref "C60") (pin "1") (pinfunction "1_1") (pintype "passive"))
      (node (ref "C61") (pin "1") (pinfunction "1_1") (pintype "passive"))
      (node (ref "C62") (pin "1") (pinfunction "1_1") (pintype "passive"))
      (node (ref "C63") (pin "1") (pinfunction "1_1") (pintype "passive"))
      (node (ref "C67") (pin "1") (pinfunction "1_1") (pintype "passive"))
      (node (ref "C69") (pin "1") (pinfunction "1_1") (pintype "passive"))
      (node (ref "C70") (pin "1") (pinfunction "1_1") (pintype "passive"))
      (node (ref "C71") (pin "1") (pinfunction "1_1") (pintype "passive"))
      (node (ref "C72") (pin "1") (pinfunction "1_1") (pintype "passive"))
      (node (ref "C73") (pin "1") (pinfunction "1_1") (pintype "passive"))
      (node (ref "C74") (pin "1") (pinfunction "1_1") (pintype "passive"))
      (node (ref "C76") (pin "1") (pinfunction "1_1") (pintype "passive"))
      (node (ref "C77") (pin "1") (pinfunction "1_1") (pintype "passive"))
      (node (ref "C8") (pin "1") (pinfunction "1_1") (pintype "passive"))
      (node (ref "C81") (pin "1") (pinfunction "1_1") (pintype "passive"))
      (node (ref "C83") (pin "1") (pinfunction "1_1") (pintype "passive"))
      (node (ref "C84") (pin "1") (pinfunction "1_1") (pintype "passive"))
      (node (ref "C85") (pin "1") (pinfunction "1_1") (pintype "passive"))
      (node (ref "C86") (pin "1") (pinfunction "1_1") (pintype "passive"))
      (node (ref "C87") (pin "1") (pinfunction "1_1") (pintype "passive"))
      (node (ref "C88") (pin "1") (pinfunction "1_1") (pintype "passive"))
      (node (ref "C89") (pin "1") (pinfunction "1_1") (pintype "passive"))
      (node (ref "C90") (pin "1") (pinfunction "1_1") (pintype "passive"))
      (node (ref "C97") (pin "1") (pinfunction "1_1") (pintype "passive"))
      (node (ref "C98") (pin "1") (pinfunction "1_1") (pintype "passive"))
      (node (ref "C99") (pin "1") (pinfunction "1_1") (pintype "passive"))
      (node (ref "L10") (pin "1") (pinfunction "1_1") (pintype "passive"))
      (node (ref "L11") (pin "1") (pinfunction "1_1") (pintype "passive"))
      (node (ref "L13") (pin "1") (pinfunction "1_1") (pintype "bidirectional"))
      (node (ref "R13") (pin "2") (pinfunction "2_2") (pintype "passive"))
      (node (ref "R15") (pin "1") (pinfunction "1_1") (pintype "passive"))
      (node (ref "R16") (pin "2") (pinfunction "2_2") (pintype "passive"))
      (node (ref "R17") (pin "1") (pinfunction "1_1") (pintype "passive"))
      (node (ref "R28") (pin "P$1") (pinfunction "1_P$1") (pintype "passive"))
      (node (ref "R30") (pin "P$2") (pinfunction "2_P$2") (pintype "passive"))
      (node (ref "R34") (pin "P$2") (pinfunction "2_P$2") (pintype "passive"))
      (node (ref "R4") (pin "P$1") (pinfunction "1_P$1") (pintype "passive"))
      (node (ref "R5") (pin "P$1") (pinfunction "1_P$1") (pintype "passive"))
      (node (ref "R6") (pin "P$1") (pinfunction "1_P$1") (pintype "passive"))
      (node (ref "R61") (pin "2") (pinfunction "2_2") (pintype "passive"))
      (node (ref "U1") (pin "B13") (pinfunction "VCCO_0_B13") (pintype "input"))
      (node (ref "U1") (pin "B4") (pinfunction "VCCO_0_B4") (pintype "input"))
      (node (ref "U1") (pin "B9") (pinfunction "VCCO_0_B9") (pintype "input"))
      (node (ref "U1") (pin "D10") (pinfunction "VCCO_0_D10") (pintype "input"))
      (node (ref "U1") (pin "D15") (pinfunction "VCCO_1_D15") (pintype "input"))
      (node (ref "U1") (pin "D2") (pinfunction "VCCO_3_D2") (pintype "input"))
      (node (ref "U1") (pin "D7") (pinfunction "VCCO_0_D7") (pintype "input"))
      (node (ref "U1") (pin "E5") (pinfunction "VCCAUX_E5") (pintype "input"))
      (node (ref "U1") (pin "F11") (pinfunction "VCCAUX_F11") (pintype "input"))
      (node (ref "U1") (pin "F8") (pinfunction "VCCAUX_F8") (pintype "input"))
      (node (ref "U1") (pin "G10") (pinfunction "VCCAUX_G10") (pintype "input"))
      (node (ref "U1") (pin "G13") (pinfunction "VCCO_1_G13") (pintype "input"))
      (node (ref "U1") (pin "G4") (pinfunction "VCCO_3_G4") (pintype "input"))
      (node (ref "U1") (pin "H6") (pinfunction "VCCAUX_H6") (pintype "input"))
      (node (ref "U1") (pin "J10") (pinfunction "VCCAUX_J10") (pintype "input"))
      (node (ref "U1") (pin "J15") (pinfunction "VCCO_1_J15") (pintype "input"))
      (node (ref "U1") (pin "J2") (pinfunction "VCCO_3_J2") (pintype "input"))
      (node (ref "U1") (pin "K13") (pinfunction "VCCO_1_K13") (pintype "input"))
      (node (ref "U1") (pin "K4") (pinfunction "VCCO_3_K4") (pintype "input"))
      (node (ref "U1") (pin "L6") (pinfunction "VCCAUX_L6") (pintype "input"))
      (node (ref "U1") (pin "L9") (pinfunction "VCCAUX_L9") (pintype "input"))
      (node (ref "U1") (pin "N10") (pinfunction "VCCO_2_N10") (pintype "input"))
      (node (ref "U1") (pin "N15") (pinfunction "VCCO_1_N15") (pintype "input"))
      (node (ref "U1") (pin "N2") (pinfunction "VCCO_3_N2") (pintype "input"))
      (node (ref "U1") (pin "N7") (pinfunction "VCCO_2_N7") (pintype "input"))
      (node (ref "U1") (pin "R13") (pinfunction "VCCO_1_R13") (pintype "input"))
      (node (ref "U1") (pin "R4") (pinfunction "VCCO_2_R4") (pintype "input"))
      (node (ref "U1") (pin "R8") (pinfunction "VCCO_2_R8") (pintype "input"))
      (node (ref "U1") (pin "T11") (pinfunction "IO_L1N_M0_CMPMISO_2_T11") (pintype "bidirectional"))
      (node (ref "U13") (pin "3") (pinfunction "NWP_3") (pintype "input"))
      (node (ref "U13") (pin "7") (pinfunction "NHOLD_7") (pintype "input"))
      (node (ref "U13") (pin "8") (pinfunction "VCC_8") (pintype "power_in"))
      (node (ref "U3") (pin "1") (pinfunction "VBAT_1") (pintype "power_in"))
      (node (ref "U3") (pin "13") (pinfunction "VDDA_13") (pintype "power_in"))
      (node (ref "U3") (pin "19") (pinfunction "VDD4_19") (pintype "bidirectional"))
      (node (ref "U3") (pin "32") (pinfunction "VDD1_32") (pintype "power_in"))
      (node (ref "U3") (pin "48") (pinfunction "VDD2_48") (pintype "power_in"))
      (node (ref "U3") (pin "64") (pinfunction "VDD3_64") (pintype "power_in"))
      (node (ref "U6") (pin "6") (pinfunction "VCC_6") (pintype "power_in"))
      (node (ref "U7") (pin "12") (pinfunction "VCCIO1_12") (pintype "power_in"))
      (node (ref "U7") (pin "24") (pinfunction "VCCIO2_24") (pintype "power_in"))
      (node (ref "U7") (pin "39") (pinfunction "VCCD_39") (pintype "bidirectional"))
      (node (ref "U7") (pin "40") (pinfunction "VREGIN_40") (pintype "power_in"))
      (node (ref "U7") (pin "46") (pinfunction "VCCIO3_46") (pintype "power_in"))
      (node (ref "X1") (pin "4") (pinfunction "4_4") (pintype "bidirectional"))
      (node (ref "X5") (pin "1") (pinfunction "1_1") (pintype "bidirectional"))
      (node (ref "X6") (pin "4") (pinfunction "4_4") (pintype "bidirectional"))
    )
    (net (code "106") (name "VDD") (class "Default")
      (node (ref "C2") (pin "1") (pinfunction "1_1") (pintype "passive"))
      (node (ref "C6") (pin "2") (pinfunction "2_2") (pintype "passive"))
      (node (ref "Q1") (pin "2") (pinfunction "S_2") (pintype "passive"))
      (node (ref "R1") (pin "2") (pinfunction "2_2") (pintype "passive"))
      (node (ref "R65") (pin "1") (pinfunction "1_1") (pintype "passive"))
      (node (ref "U2") (pin "2") (pinfunction "RUN/SS1_2") (pintype "bidirectional"))
      (node (ref "U2") (pin "3") (pinfunction "VIN_3") (pintype "bidirectional"))
      (node (ref "U2") (pin "6") (pinfunction "MODE/SYNC_6") (pintype "bidirectional"))
      (node (ref "U2") (pin "9") (pinfunction "RUN/SS2_9") (pintype "bidirectional"))
    )
    (net (code "107") (name "V_USB") (class "Default")
      (node (ref "D1") (pin "1") (pinfunction "1_1") (pintype "bidirectional"))
      (node (ref "J6") (pin "PIN_1") (pinfunction "1_PIN_1") (pintype "input"))
      (node (ref "R8") (pin "P$2") (pinfunction "2_P$2") (pintype "passive"))
      (node (ref "R9") (pin "P$1") (pinfunction "1_P$1") (pintype "passive"))
      (node (ref "U3") (pin "26") (pinfunction "PB0-ADC8/TIM3CH3-TIM1CH2N_26") (pintype "bidirectional"))
    )
    (net (code "108") (name "unconnected-(J6-4-PadPIN_4)") (class "Default")
      (node (ref "J6") (pin "PIN_4") (pinfunction "4_PIN_4") (pintype "input"))
    )
    (net (code "109") (name "unconnected-(U1A-IO_L1N_VREF_0-PadA4)") (class "Default")
      (node (ref "U1") (pin "A4") (pinfunction "IO_L1N_VREF_0_A4") (pintype "bidirectional"))
    )
    (net (code "110") (name "unconnected-(U1A-IO_L2P_0-PadB5)") (class "Default")
      (node (ref "U1") (pin "B5") (pinfunction "IO_L2P_0_B5") (pintype "bidirectional"))
    )
    (net (code "111") (name "unconnected-(U1A-IO_L3N_0-PadC5)") (class "Default")
      (node (ref "U1") (pin "C5") (pinfunction "IO_L3N_0_C5") (pintype "bidirectional"))
    )
    (net (code "112") (name "unconnected-(U1A-IO_L3P_0-PadD5)") (class "Default")
      (node (ref "U1") (pin "D5") (pinfunction "IO_L3P_0_D5") (pintype "bidirectional"))
    )
    (net (code "113") (name "unconnected-(U1A-IO_L4N_0-PadA6)") (class "Default")
      (node (ref "U1") (pin "A6") (pinfunction "IO_L4N_0_A6") (pintype "bidirectional"))
    )
    (net (code "114") (name "unconnected-(U1A-IO_L4P_0-PadB6)") (class "Default")
      (node (ref "U1") (pin "B6") (pinfunction "IO_L4P_0_B6") (pintype "bidirectional"))
    )
    (net (code "115") (name "unconnected-(U1A-IO_L5N_0-PadE6)") (class "Default")
      (node (ref "U1") (pin "E6") (pinfunction "IO_L5N_0_E6") (pintype "bidirectional"))
    )
    (net (code "116") (name "unconnected-(U1A-IO_L5P_0-PadF7)") (class "Default")
      (node (ref "U1") (pin "F7") (pinfunction "IO_L5P_0_F7") (pintype "bidirectional"))
    )
    (net (code "117") (name "unconnected-(U1A-IO_L6P_0-PadC7)") (class "Default")
      (node (ref "U1") (pin "C7") (pinfunction "IO_L6P_0_C7") (pintype "bidirectional"))
    )
    (net (code "118") (name "unconnected-(U1A-IO_L7N_0-PadC6)") (class "Default")
      (node (ref "U1") (pin "C6") (pinfunction "IO_L7N_0_C6") (pintype "bidirectional"))
    )
    (net (code "119") (name "unconnected-(U1A-IO_L7P_0-PadD6)") (class "Default")
      (node (ref "U1") (pin "D6") (pinfunction "IO_L7P_0_D6") (pintype "bidirectional"))
    )
    (net (code "120") (name "unconnected-(U1A-IO_L33N_0-PadA8)") (class "Default")
      (node (ref "U1") (pin "A8") (pinfunction "IO_L33N_0_A8") (pintype "bidirectional"))
    )
    (net (code "121") (name "unconnected-(U1A-IO_L33P_0-PadB8)") (class "Default")
      (node (ref "U1") (pin "B8") (pinfunction "IO_L33P_0_B8") (pintype "bidirectional"))
    )
    (net (code "122") (name "unconnected-(U1A-IO_L34P_GCLK19_0-PadC9)") (class "Default")
      (node (ref "U1") (pin "C9") (pinfunction "IO_L34P_GCLK19_0_C9") (pintype "bidirectional"))
    )
    (net (code "123") (name "unconnected-(U1A-IO_L36N_GCLK14_0-PadE8)") (class "Default")
      (node (ref "U1") (pin "E8") (pinfunction "IO_L36N_GCLK14_0_E8") (pintype "bidirectional"))
    )
    (net (code "124") (name "unconnected-(U1A-IO_L36P_GCLK15_0-PadE7)") (class "Default")
      (node (ref "U1") (pin "E7") (pinfunction "IO_L36P_GCLK15_0_E7") (pintype "bidirectional"))
    )
    (net (code "125") (name "unconnected-(U1A-IO_L37P_GCLK13_0-PadE10)") (class "Default")
      (node (ref "U1") (pin "E10") (pinfunction "IO_L37P_GCLK13_0_E10") (pintype "bidirectional"))
    )
    (net (code "126") (name "unconnected-(U1A-IO_L38N_VREF_0-PadC8)") (class "Default")
      (node (ref "U1") (pin "C8") (pinfunction "IO_L38N_VREF_0_C8") (pintype "bidirectional"))
    )
    (net (code "127") (name "unconnected-(U1A-IO_L38P_0-PadD8)") (class "Default")
      (node (ref "U1") (pin "D8") (pinfunction "IO_L38P_0_D8") (pintype "bidirectional"))
    )
    (net (code "128") (name "unconnected-(U1A-IO_L39N_0-PadA11)") (class "Default")
      (node (ref "U1") (pin "A11") (pinfunction "IO_L39N_0_A11") (pintype "bidirectional"))
    )
    (net (code "129") (name "unconnected-(U1A-IO_L40N_0-PadD9)") (class "Default")
      (node (ref "U1") (pin "D9") (pinfunction "IO_L40N_0_D9") (pintype "bidirectional"))
    )
    (net (code "130") (name "unconnected-(U1A-IO_L40P_0-PadF9)") (class "Default")
      (node (ref "U1") (pin "F9") (pinfunction "IO_L40P_0_F9") (pintype "bidirectional"))
    )
    (net (code "131") (name "unconnected-(U1A-IO_L62P_0-PadB12)") (class "Default")
      (node (ref "U1") (pin "B12") (pinfunction "IO_L62P_0_B12") (pintype "bidirectional"))
    )
    (net (code "132") (name "unconnected-(U1A-IO_L63N_SCP6_0-PadA13)") (class "Default")
      (node (ref "U1") (pin "A13") (pinfunction "IO_L63N_SCP6_0_A13") (pintype "bidirectional"))
    )
    (net (code "133") (name "unconnected-(U1A-IO_L63P_SCP7_0-PadC13)") (class "Default")
      (node (ref "U1") (pin "C13") (pinfunction "IO_L63P_SCP7_0_C13") (pintype "bidirectional"))
    )
    (net (code "134") (name "unconnected-(U1A-IO_L64N_SCP4_0-PadE11)") (class "Default")
      (node (ref "U1") (pin "E11") (pinfunction "IO_L64N_SCP4_0_E11") (pintype "bidirectional"))
    )
    (net (code "135") (name "unconnected-(U1A-IO_L64P_SCP5_0-PadF10)") (class "Default")
      (node (ref "U1") (pin "F10") (pinfunction "IO_L64P_SCP5_0_F10") (pintype "bidirectional"))
    )
    (net (code "136") (name "unconnected-(U1A-IO_L65N_SCP2_0-PadA14)") (class "Default")
      (node (ref "U1") (pin "A14") (pinfunction "IO_L65N_SCP2_0_A14") (pintype "bidirectional"))
    )
    (net (code "137") (name "unconnected-(U1A-IO_L65P_SCP3_0-PadB14)") (class "Default")
      (node (ref "U1") (pin "B14") (pinfunction "IO_L65P_SCP3_0_B14") (pintype "bidirectional"))
    )
    (net (code "138") (name "unconnected-(U1A-IO_L66N_SCP0_0-PadD12)") (class "Default")
      (node (ref "U1") (pin "D12") (pinfunction "IO_L66N_SCP0_0_D12") (pintype "bidirectional"))
    )
    (net (code "139") (name "unconnected-(U1A-IO_L66P_SCP1_0-PadD11)") (class "Default")
      (node (ref "U1") (pin "D11") (pinfunction "IO_L66P_SCP1_0_D11") (pintype "bidirectional"))
    )
    (net (code "140") (name "unconnected-(U1B-IO_L1N_A24_VREF_1-PadE12)") (class "Default")
      (node (ref "U1") (pin "E12") (pinfunction "IO_L1N_A24_VREF_1_E12") (pintype "bidirectional"))
    )
    (net (code "141") (name "unconnected-(U1B-IO_L1P_A25_1-PadE13)") (class "Default")
      (node (ref "U1") (pin "E13") (pinfunction "IO_L1P_A25_1_E13") (pintype "bidirectional"))
    )
    (net (code "142") (name "unconnected-(U1B-IO_L29N_A22_M1A14_1-PadB16)") (class "Default")
      (node (ref "U1") (pin "B16") (pinfunction "IO_L29N_A22_M1A14_1_B16") (pintype "bidirectional"))
    )
    (net (code "143") (name "unconnected-(U1B-IO_L29P_A23_M1A13_1-PadB15)") (class "Default")
      (node (ref "U1") (pin "B15") (pinfunction "IO_L29P_A23_M1A13_1_B15") (pintype "bidirectional"))
    )
    (net (code "144") (name "unconnected-(U1B-IO_L30N_A20_M1A11_1-PadG11)") (class "Default")
      (node (ref "U1") (pin "G11") (pinfunction "IO_L30N_A20_M1A11_1_G11") (pintype "bidirectional"))
    )
    (net (code "145") (name "unconnected-(U1B-IO_L30P_A21_M1RESET_1-PadF12)") (class "Default")
      (node (ref "U1") (pin "F12") (pinfunction "IO_L30P_A21_M1RESET_1_F12") (pintype "bidirectional"))
    )
    (net (code "146") (name "unconnected-(U1B-IO_L31N_A18_M1A12_1-PadD16)") (class "Default")
      (node (ref "U1") (pin "D16") (pinfunction "IO_L31N_A18_M1A12_1_D16") (pintype "bidirectional"))
    )
    (net (code "147") (name "unconnected-(U1B-IO_L31P_A19_M1CKE_1-PadD14)") (class "Default")
      (node (ref "U1") (pin "D14") (pinfunction "IO_L31P_A19_M1CKE_1_D14") (pintype "bidirectional"))
    )
    (net (code "148") (name "unconnected-(U1B-IO_L32N_A16_M1A9_1-PadF14)") (class "Default")
      (node (ref "U1") (pin "F14") (pinfunction "IO_L32N_A16_M1A9_1_F14") (pintype "bidirectional"))
    )
    (net (code "149") (name "unconnected-(U1B-IO_L32P_A17_M1A8_1-PadF13)") (class "Default")
      (node (ref "U1") (pin "F13") (pinfunction "IO_L32P_A17_M1A8_1_F13") (pintype "bidirectional"))
    )
    (net (code "150") (name "unconnected-(U1B-IO_L33N_A14_M1A4_1-PadC16)") (class "Default")
      (node (ref "U1") (pin "C16") (pinfunction "IO_L33N_A14_M1A4_1_C16") (pintype "bidirectional"))
    )
    (net (code "151") (name "unconnected-(U1B-IO_L33P_A15_M1A10_1-PadC15)") (class "Default")
      (node (ref "U1") (pin "C15") (pinfunction "IO_L33P_A15_M1A10_1_C15") (pintype "bidirectional"))
    )
    (net (code "152") (name "unconnected-(U1B-IO_L36N_A8_M1BA1_1-PadG16)") (class "Default")
      (node (ref "U1") (pin "G16") (pinfunction "IO_L36N_A8_M1BA1_1_G16") (pintype "bidirectional"))
    )
    (net (code "153") (name "unconnected-(U1B-IO_L36P_A9_M1BA0_1-PadG14)") (class "Default")
      (node (ref "U1") (pin "G14") (pinfunction "IO_L36P_A9_M1BA0_1_G14") (pintype "bidirectional"))
    )
    (net (code "154") (name "unconnected-(U1B-IO_L37N_A6_M1A1_1-PadH16)") (class "Default")
      (node (ref "U1") (pin "H16") (pinfunction "IO_L37N_A6_M1A1_1_H16") (pintype "bidirectional"))
    )
    (net (code "155") (name "unconnected-(U1B-IO_L37P_A7_M1A0_1-PadH15)") (class "Default")
      (node (ref "U1") (pin "H15") (pinfunction "IO_L37P_A7_M1A0_1_H15") (pintype "bidirectional"))
    )
    (net (code "156") (name "unconnected-(U1B-IO_L38N_A4_M1CLKN_1-PadH11)") (class "Default")
      (node (ref "U1") (pin "H11") (pinfunction "IO_L38N_A4_M1CLKN_1_H11") (pintype "bidirectional"))
    )
    (net (code "157") (name "unconnected-(U1B-IO_L38P_A5_M1CLK_1-PadG12)") (class "Default")
      (node (ref "U1") (pin "G12") (pinfunction "IO_L38P_A5_M1CLK_1_G12") (pintype "bidirectional"))
    )
    (net (code "158") (name "unconnected-(U1B-IO_L39N_M1ODT_1-PadH14)") (class "Default")
      (node (ref "U1") (pin "H14") (pinfunction "IO_L39N_M1ODT_1_H14") (pintype "bidirectional"))
    )
    (net (code "159") (name "unconnected-(U1B-IO_L39P_M1A3_1-PadH13)") (class "Default")
      (node (ref "U1") (pin "H13") (pinfunction "IO_L39P_M1A3_1_H13") (pintype "bidirectional"))
    )
    (net (code "160") (name "unconnected-(U1B-IO_L40N_GCLK10_M1A6_1-PadJ12)") (class "Default")
      (node (ref "U1") (pin "J12") (pinfunction "IO_L40N_GCLK10_M1A6_1_J12") (pintype "bidirectional"))
    )
    (net (code "161") (name "unconnected-(U1B-IO_L40P_GCLK11_M1A5_1-PadJ11)") (class "Default")
      (node (ref "U1") (pin "J11") (pinfunction "IO_L40P_GCLK11_M1A5_1_J11") (pintype "bidirectional"))
    )
    (net (code "162") (name "unconnected-(U1B-IO_L41P_GCLK9_IRDY1_M1RASN_1-PadJ13)") (class "Default")
      (node (ref "U1") (pin "J13") (pinfunction "IO_L41P_GCLK9_IRDY1_M1RASN_1_J13") (pintype "bidirectional"))
    )
    (net (code "163") (name "unconnected-(U1B-IO_L42N_GCLK6_TRDY1_M1LDM_1-PadK11)") (class "Default")
      (node (ref "U1") (pin "K11") (pinfunction "IO_L42N_GCLK6_TRDY1_M1LDM_1_K11") (pintype "bidirectional"))
    )
    (net (code "164") (name "unconnected-(U1B-IO_L42P_GCLK7_M1UDM_1-PadK12)") (class "Default")
      (node (ref "U1") (pin "K12") (pinfunction "IO_L42P_GCLK7_M1UDM_1_K12") (pintype "bidirectional"))
    )
    (net (code "165") (name "unconnected-(U1B-IO_L43N_GCLK4_M1DQ5_1-PadJ16)") (class "Default")
      (node (ref "U1") (pin "J16") (pinfunction "IO_L43N_GCLK4_M1DQ5_1_J16") (pintype "bidirectional"))
    )
    (net (code "166") (name "unconnected-(U1B-IO_L48N_M1DQ9_1-PadP16)") (class "Default")
      (node (ref "U1") (pin "P16") (pinfunction "IO_L48N_M1DQ9_1_P16") (pintype "bidirectional"))
    )
    (net (code "167") (name "unconnected-(U1B-IO_L48P_HDC_M1DQ8_1-PadP15)") (class "Default")
      (node (ref "U1") (pin "P15") (pinfunction "IO_L48P_HDC_M1DQ8_1_P15") (pintype "bidirectional"))
    )
    (net (code "168") (name "unconnected-(U1B-IO_L49N_M1DQ11_1-PadR16)") (class "Default")
      (node (ref "U1") (pin "R16") (pinfunction "IO_L49N_M1DQ11_1_R16") (pintype "bidirectional"))
    )
    (net (code "169") (name "unconnected-(U1B-IO_L49P_M1DQ10_1-PadR15)") (class "Default")
      (node (ref "U1") (pin "R15") (pinfunction "IO_L49P_M1DQ10_1_R15") (pintype "bidirectional"))
    )
    (net (code "170") (name "unconnected-(U1B-IO_L50N_M1UDQSN_1-PadT15)") (class "Default")
      (node (ref "U1") (pin "T15") (pinfunction "IO_L50N_M1UDQSN_1_T15") (pintype "bidirectional"))
    )
    (net (code "171") (name "unconnected-(U1B-IO_L50P_M1UDQS_1-PadR14)") (class "Default")
      (node (ref "U1") (pin "R14") (pinfunction "IO_L50P_M1UDQS_1_R14") (pintype "bidirectional"))
    )
    (net (code "172") (name "unconnected-(U1B-IO_L51N_M1DQ13_1-PadT13)") (class "Default")
      (node (ref "U1") (pin "T13") (pinfunction "IO_L51N_M1DQ13_1_T13") (pintype "bidirectional"))
    )
    (net (code "173") (name "unconnected-(U1B-IO_L51P_M1DQ12_1-PadT14)") (class "Default")
      (node (ref "U1") (pin "T14") (pinfunction "IO_L51P_M1DQ12_1_T14") (pintype "bidirectional"))
    )
    (net (code "174") (name "unconnected-(U1B-IO_L52N_M1DQ15_1-PadT12)") (class "Default")
      (node (ref "U1") (pin "T12") (pinfunction "IO_L52N_M1DQ15_1_T12") (pintype "bidirectional"))
    )
    (net (code "175") (name "unconnected-(U1B-IO_L52P_M1DQ14_1-PadR12)") (class "Default")
      (node (ref "U1") (pin "R12") (pinfunction "IO_L52P_M1DQ14_1_R12") (pintype "bidirectional"))
    )
    (net (code "176") (name "unconnected-(U1B-IO_L53N_VREF_1-PadL13)") (class "Default")
      (node (ref "U1") (pin "L13") (pinfunction "IO_L53N_VREF_1_L13") (pintype "bidirectional"))
    )
    (net (code "177") (name "unconnected-(U1B-IO_L53P_1-PadL12)") (class "Default")
      (node (ref "U1") (pin "L12") (pinfunction "IO_L53P_1_L12") (pintype "bidirectional"))
    )
    (net (code "178") (name "unconnected-(U1B-IO_L74P_AWAKE_1-PadM13)") (class "Default")
      (node (ref "U1") (pin "M13") (pinfunction "IO_L74P_AWAKE_1_M13") (pintype "bidirectional"))
    )
    (net (code "179") (name "unconnected-(U1C-CMPCS_B_2-PadL11)") (class "Default")
      (node (ref "U1") (pin "L11") (pinfunction "CMPCS_B_2_L11") (pintype "bidirectional"))
    )
    (net (code "180") (name "unconnected-(U1C-IO_L2N_CMPMOSI_2-PadM11)") (class "Default")
      (node (ref "U1") (pin "M11") (pinfunction "IO_L2N_CMPMOSI_2_M11") (pintype "bidirectional"))
    )
    (net (code "181") (name "unconnected-(U1C-IO_L2P_CMPCLK_2-PadM12)") (class "Default")
      (node (ref "U1") (pin "M12") (pinfunction "IO_L2P_CMPCLK_2_M12") (pintype "bidirectional"))
    )
    (net (code "182") (name "unconnected-(U1C-IO_L12N_D2_MISO3_2-PadP12)") (class "Default")
      (node (ref "U1") (pin "P12") (pinfunction "IO_L12N_D2_MISO3_2_P12") (pintype "bidirectional"))
    )
    (net (code "183") (name "unconnected-(U1C-IO_L12P_D1_MISO2_2-PadN12)") (class "Default")
      (node (ref "U1") (pin "N12") (pinfunction "IO_L12P_D1_MISO2_2_N12") (pintype "bidirectional"))
    )
    (net (code "184") (name "unconnected-(U1C-IO_L13N_D10_2-PadP11)") (class "Default")
      (node (ref "U1") (pin "P11") (pinfunction "IO_L13N_D10_2_P11") (pintype "bidirectional"))
    )
    (net (code "185") (name "unconnected-(U1C-IO_L14P_D11_2-PadN9)") (class "Default")
      (node (ref "U1") (pin "N9") (pinfunction "IO_L14P_D11_2_N9") (pintype "bidirectional"))
    )
    (net (code "186") (name "unconnected-(U1C-IO_L16N_VREF_2-PadM10)") (class "Default")
      (node (ref "U1") (pin "M10") (pinfunction "IO_L16N_VREF_2_M10") (pintype "bidirectional"))
    )
    (net (code "187") (name "unconnected-(U1C-IO_L16P_2-PadL10)") (class "Default")
      (node (ref "U1") (pin "L10") (pinfunction "IO_L16P_2_L10") (pintype "bidirectional"))
    )
    (net (code "188") (name "unconnected-(U1C-IO_L23N_2-PadT9)") (class "Default")
      (node (ref "U1") (pin "T9") (pinfunction "IO_L23N_2_T9") (pintype "bidirectional"))
    )
    (net (code "189") (name "unconnected-(U1C-IO_L23P_2-PadR9)") (class "Default")
      (node (ref "U1") (pin "R9") (pinfunction "IO_L23P_2_R9") (pintype "bidirectional"))
    )
    (net (code "190") (name "unconnected-(U1C-IO_L29N_GCLK2_2-PadN8)") (class "Default")
      (node (ref "U1") (pin "N8") (pinfunction "IO_L29N_GCLK2_2_N8") (pintype "bidirectional"))
    )
    (net (code "191") (name "unconnected-(U1C-IO_L29P_GCLK3_2-PadM9)") (class "Default")
      (node (ref "U1") (pin "M9") (pinfunction "IO_L29P_GCLK3_2_M9") (pintype "bidirectional"))
    )
    (net (code "192") (name "unconnected-(U1C-IO_L30N_GCLK0_USERCCLK_2-PadT8)") (class "Default")
      (node (ref "U1") (pin "T8") (pinfunction "IO_L30N_GCLK0_USERCCLK_2_T8") (pintype "bidirectional"))
    )
    (net (code "193") (name "unconnected-(U1C-IO_L30P_GCLK1_D13_2-PadP8)") (class "Default")
      (node (ref "U1") (pin "P8") (pinfunction "IO_L30P_GCLK1_D13_2_P8") (pintype "bidirectional"))
    )
    (net (code "194") (name "unconnected-(U1C-IO_L31N_GCLK30_D15_2-PadM7)") (class "Default")
      (node (ref "U1") (pin "M7") (pinfunction "IO_L31N_GCLK30_D15_2_M7") (pintype "bidirectional"))
    )
    (net (code "195") (name "unconnected-(U1C-IO_L31P_GCLK31_D14_2-PadP7)") (class "Default")
      (node (ref "U1") (pin "P7") (pinfunction "IO_L31P_GCLK31_D14_2_P7") (pintype "bidirectional"))
    )
    (net (code "196") (name "unconnected-(U1C-IO_L32N_GCLK28_2-PadT7)") (class "Default")
      (node (ref "U1") (pin "T7") (pinfunction "IO_L32N_GCLK28_2_T7") (pintype "bidirectional"))
    )
    (net (code "197") (name "unconnected-(U1C-IO_L32P_GCLK29_2-PadR7)") (class "Default")
      (node (ref "U1") (pin "R7") (pinfunction "IO_L32P_GCLK29_2_R7") (pintype "bidirectional"))
    )
    (net (code "198") (name "unconnected-(U1C-IO_L47N_2-PadT6)") (class "Default")
      (node (ref "U1") (pin "T6") (pinfunction "IO_L47N_2_T6") (pintype "bidirectional"))
    )
    (net (code "199") (name "unconnected-(U1C-IO_L47P_2-PadP6)") (class "Default")
      (node (ref "U1") (pin "P6") (pinfunction "IO_L47P_2_P6") (pintype "bidirectional"))
    )
    (net (code "200") (name "unconnected-(U1C-IO_L48N_RDWR_B_VREF_2-PadT5)") (class "Default")
      (node (ref "U1") (pin "T5") (pinfunction "IO_L48N_RDWR_B_VREF_2_T5") (pintype "bidirectional"))
    )
    (net (code "201") (name "unconnected-(U1C-IO_L48P_D7_2-PadR5)") (class "Default")
      (node (ref "U1") (pin "R5") (pinfunction "IO_L48P_D7_2_R5") (pintype "bidirectional"))
    )
    (net (code "202") (name "unconnected-(U1C-IO_L49N_D4_2-PadP5)") (class "Default")
      (node (ref "U1") (pin "P5") (pinfunction "IO_L49N_D4_2_P5") (pintype "bidirectional"))
    )
    (net (code "203") (name "unconnected-(U1C-IO_L49P_D3_2-PadN5)") (class "Default")
      (node (ref "U1") (pin "N5") (pinfunction "IO_L49P_D3_2_N5") (pintype "bidirectional"))
    )
    (net (code "204") (name "unconnected-(U1C-IO_L62N_D6_2-PadL7)") (class "Default")
      (node (ref "U1") (pin "L7") (pinfunction "IO_L62N_D6_2_L7") (pintype "bidirectional"))
    )
    (net (code "205") (name "unconnected-(U1C-IO_L62P_D5_2-PadL8)") (class "Default")
      (node (ref "U1") (pin "L8") (pinfunction "IO_L62P_D5_2_L8") (pintype "bidirectional"))
    )
    (net (code "206") (name "unconnected-(U1C-IO_L63N_2-PadT4)") (class "Default")
      (node (ref "U1") (pin "T4") (pinfunction "IO_L63N_2_T4") (pintype "bidirectional"))
    )
    (net (code "207") (name "unconnected-(U1C-IO_L63P_2-PadP4)") (class "Default")
      (node (ref "U1") (pin "P4") (pinfunction "IO_L63P_2_P4") (pintype "bidirectional"))
    )
    (net (code "208") (name "unconnected-(U1C-IO_L64N_D9_2-PadN6)") (class "Default")
      (node (ref "U1") (pin "N6") (pinfunction "IO_L64N_D9_2_N6") (pintype "bidirectional"))
    )
    (net (code "209") (name "unconnected-(U1C-IO_L64P_D8_2-PadM6)") (class "Default")
      (node (ref "U1") (pin "M6") (pinfunction "IO_L64P_D8_2_M6") (pintype "bidirectional"))
    )
    (net (code "210") (name "unconnected-(U1D-IO_L1N_VREF_3-PadM3)") (class "Default")
      (node (ref "U1") (pin "M3") (pinfunction "IO_L1N_VREF_3_M3") (pintype "bidirectional"))
    )
    (net (code "211") (name "unconnected-(U1D-IO_L1P_3-PadM4)") (class "Default")
      (node (ref "U1") (pin "M4") (pinfunction "IO_L1P_3_M4") (pintype "bidirectional"))
    )
    (net (code "212") (name "unconnected-(U1D-IO_L2N_3-PadN4)") (class "Default")
      (node (ref "U1") (pin "N4") (pinfunction "IO_L2N_3_N4") (pintype "bidirectional"))
    )
    (net (code "213") (name "unconnected-(U1D-IO_L2P_3-PadM5)") (class "Default")
      (node (ref "U1") (pin "M5") (pinfunction "IO_L2P_3_M5") (pintype "bidirectional"))
    )
    (net (code "214") (name "unconnected-(U1D-IO_L32N_M3DQ15_3-PadR1)") (class "Default")
      (node (ref "U1") (pin "R1") (pinfunction "IO_L32N_M3DQ15_3_R1") (pintype "bidirectional"))
    )
    (net (code "215") (name "unconnected-(U1D-IO_L32P_M3DQ14_3-PadR2)") (class "Default")
      (node (ref "U1") (pin "R2") (pinfunction "IO_L32P_M3DQ14_3_R2") (pintype "bidirectional"))
    )
    (net (code "216") (name "unconnected-(U1D-IO_L33N_M3DQ13_3-PadP1)") (class "Default")
      (node (ref "U1") (pin "P1") (pinfunction "IO_L33N_M3DQ13_3_P1") (pintype "bidirectional"))
    )
    (net (code "217") (name "unconnected-(U1D-IO_L33P_M3DQ12_3-PadP2)") (class "Default")
      (node (ref "U1") (pin "P2") (pinfunction "IO_L33P_M3DQ12_3_P2") (pintype "bidirectional"))
    )
    (net (code "218") (name "unconnected-(U1D-IO_L34N_M3UDQSN_3-PadN1)") (class "Default")
      (node (ref "U1") (pin "N1") (pinfunction "IO_L34N_M3UDQSN_3_N1") (pintype "bidirectional"))
    )
    (net (code "219") (name "unconnected-(U1D-IO_L34P_M3UDQS_3-PadN3)") (class "Default")
      (node (ref "U1") (pin "N3") (pinfunction "IO_L34P_M3UDQS_3_N3") (pintype "bidirectional"))
    )
    (net (code "220") (name "unconnected-(U1D-IO_L35N_M3DQ11_3-PadM1)") (class "Default")
      (node (ref "U1") (pin "M1") (pinfunction "IO_L35N_M3DQ11_3_M1") (pintype "bidirectional"))
    )
    (net (code "221") (name "unconnected-(U1D-IO_L35P_M3DQ10_3-PadM2)") (class "Default")
      (node (ref "U1") (pin "M2") (pinfunction "IO_L35P_M3DQ10_3_M2") (pintype "bidirectional"))
    )
    (net (code "222") (name "unconnected-(U1D-IO_L36P_M3DQ8_3-PadL3)") (class "Default")
      (node (ref "U1") (pin "L3") (pinfunction "IO_L36P_M3DQ8_3_L3") (pintype "bidirectional"))
    )
    (net (code "223") (name "unconnected-(U1D-IO_L37N_M3DQ1_3-PadK1)") (class "Default")
      (node (ref "U1") (pin "K1") (pinfunction "IO_L37N_M3DQ1_3_K1") (pintype "bidirectional"))
    )
    (net (code "224") (name "unconnected-(U1D-IO_L37P_M3DQ0_3-PadK2)") (class "Default")
      (node (ref "U1") (pin "K2") (pinfunction "IO_L37P_M3DQ0_3_K2") (pintype "bidirectional"))
    )
    (net (code "225") (name "unconnected-(U1D-IO_L38P_M3DQ2_3-PadJ3)") (class "Default")
      (node (ref "U1") (pin "J3") (pinfunction "IO_L38P_M3DQ2_3_J3") (pintype "bidirectional"))
    )
    (net (code "226") (name "unconnected-(U1D-IO_L39N_M3LDQSN_3-PadH1)") (class "Default")
      (node (ref "U1") (pin "H1") (pinfunction "IO_L39N_M3LDQSN_3_H1") (pintype "bidirectional"))
    )
    (net (code "227") (name "unconnected-(U1D-IO_L39P_M3LDQS_3-PadH2)") (class "Default")
      (node (ref "U1") (pin "H2") (pinfunction "IO_L39P_M3LDQS_3_H2") (pintype "bidirectional"))
    )
    (net (code "228") (name "unconnected-(U1D-IO_L40P_M3DQ6_3-PadG3)") (class "Default")
      (node (ref "U1") (pin "G3") (pinfunction "IO_L40P_M3DQ6_3_G3") (pintype "bidirectional"))
    )
    (net (code "229") (name "unconnected-(U1D-IO_L41P_GCLK27_M3DQ4_3-PadF2)") (class "Default")
      (node (ref "U1") (pin "F2") (pinfunction "IO_L41P_GCLK27_M3DQ4_3_F2") (pintype "bidirectional"))
    )
    (net (code "230") (name "unconnected-(U1D-IO_L42N_GCLK24_M3LDM_3-PadJ4)") (class "Default")
      (node (ref "U1") (pin "J4") (pinfunction "IO_L42N_GCLK24_M3LDM_3_J4") (pintype "bidirectional"))
    )
    (net (code "231") (name "unconnected-(U1D-IO_L42P_GCLK25_TRDY2_M3UDM_3-PadK3)") (class "Default")
      (node (ref "U1") (pin "K3") (pinfunction "IO_L42P_GCLK25_TRDY2_M3UDM_3_K3") (pintype "bidirectional"))
    )
    (net (code "232") (name "unconnected-(U1D-IO_L43N_GCLK22_IRDY2_M3CASN_3-PadH5)") (class "Default")
      (node (ref "U1") (pin "H5") (pinfunction "IO_L43N_GCLK22_IRDY2_M3CASN_3_H5") (pintype "bidirectional"))
    )
    (net (code "233") (name "unconnected-(U1D-IO_L43P_GCLK23_M3RASN_3-PadJ6)") (class "Default")
      (node (ref "U1") (pin "J6") (pinfunction "IO_L43P_GCLK23_M3RASN_3_J6") (pintype "bidirectional"))
    )
    (net (code "234") (name "unconnected-(U1D-IO_L44N_GCLK20_M3A6_3-PadH3)") (class "Default")
      (node (ref "U1") (pin "H3") (pinfunction "IO_L44N_GCLK20_M3A6_3_H3") (pintype "bidirectional"))
    )
    (net (code "235") (name "unconnected-(U1D-IO_L44P_GCLK21_M3A5_3-PadH4)") (class "Default")
      (node (ref "U1") (pin "H4") (pinfunction "IO_L44P_GCLK21_M3A5_3_H4") (pintype "bidirectional"))
    )
    (net (code "236") (name "unconnected-(U1D-IO_L45N_M3ODT_3-PadL5)") (class "Default")
      (node (ref "U1") (pin "L5") (pinfunction "IO_L45N_M3ODT_3_L5") (pintype "bidirectional"))
    )
    (net (code "237") (name "unconnected-(U1D-IO_L45P_M3A3_3-PadL4)") (class "Default")
      (node (ref "U1") (pin "L4") (pinfunction "IO_L45P_M3A3_3_L4") (pintype "bidirectional"))
    )
    (net (code "238") (name "unconnected-(U1D-IO_L46N_M3CLKN_3-PadE1)") (class "Default")
      (node (ref "U1") (pin "E1") (pinfunction "IO_L46N_M3CLKN_3_E1") (pintype "bidirectional"))
    )
    (net (code "239") (name "unconnected-(U1D-IO_L46P_M3CLK_3-PadE2)") (class "Default")
      (node (ref "U1") (pin "E2") (pinfunction "IO_L46P_M3CLK_3_E2") (pintype "bidirectional"))
    )
    (net (code "240") (name "unconnected-(U1D-IO_L47N_M3A1_3-PadK6)") (class "Default")
      (node (ref "U1") (pin "K6") (pinfunction "IO_L47N_M3A1_3_K6") (pintype "bidirectional"))
    )
    (net (code "241") (name "unconnected-(U1D-IO_L47P_M3A0_3-PadK5)") (class "Default")
      (node (ref "U1") (pin "K5") (pinfunction "IO_L47P_M3A0_3_K5") (pintype "bidirectional"))
    )
    (net (code "242") (name "unconnected-(U1D-IO_L48N_M3BA1_3-PadC2)") (class "Default")
      (node (ref "U1") (pin "C2") (pinfunction "IO_L48N_M3BA1_3_C2") (pintype "bidirectional"))
    )
    (net (code "243") (name "unconnected-(U1D-IO_L48P_M3BA0_3-PadC3)") (class "Default")
      (node (ref "U1") (pin "C3") (pinfunction "IO_L48P_M3BA0_3_C3") (pintype "bidirectional"))
    )
    (net (code "244") (name "unconnected-(U1D-IO_L49P_M3A7_3-PadD3)") (class "Default")
      (node (ref "U1") (pin "D3") (pinfunction "IO_L49P_M3A7_3_D3") (pintype "bidirectional"))
    )
    (net (code "245") (name "unconnected-(U1D-IO_L51N_M3A4_3-PadG5)") (class "Default")
      (node (ref "U1") (pin "G5") (pinfunction "IO_L51N_M3A4_3_G5") (pintype "bidirectional"))
    )
    (net (code "246") (name "unconnected-(U1D-IO_L51P_M3A10_3-PadG6)") (class "Default")
      (node (ref "U1") (pin "G6") (pinfunction "IO_L51P_M3A10_3_G6") (pintype "bidirectional"))
    )
    (net (code "247") (name "unconnected-(U1D-IO_L52N_M3A9_3-PadA2)") (class "Default")
      (node (ref "U1") (pin "A2") (pinfunction "IO_L52N_M3A9_3_A2") (pintype "bidirectional"))
    )
    (net (code "248") (name "unconnected-(U1D-IO_L52P_M3A8_3-PadB2)") (class "Default")
      (node (ref "U1") (pin "B2") (pinfunction "IO_L52P_M3A8_3_B2") (pintype "bidirectional"))
    )
    (net (code "249") (name "unconnected-(U1D-IO_L53N_M3A12_3-PadF3)") (class "Default")
      (node (ref "U1") (pin "F3") (pinfunction "IO_L53N_M3A12_3_F3") (pintype "bidirectional"))
    )
    (net (code "250") (name "unconnected-(U1D-IO_L53P_M3CKE_3-PadF4)") (class "Default")
      (node (ref "U1") (pin "F4") (pinfunction "IO_L53P_M3CKE_3_F4") (pintype "bidirectional"))
    )
    (net (code "251") (name "unconnected-(U1D-IO_L54N_M3A11_3-PadE3)") (class "Default")
      (node (ref "U1") (pin "E3") (pinfunction "IO_L54N_M3A11_3_E3") (pintype "bidirectional"))
    )
    (net (code "252") (name "unconnected-(U1D-IO_L54P_M3RESET_3-PadE4)") (class "Default")
      (node (ref "U1") (pin "E4") (pinfunction "IO_L54P_M3RESET_3_E4") (pintype "bidirectional"))
    )
    (net (code "253") (name "unconnected-(U1D-IO_L55N_M3A14_3-PadF5)") (class "Default")
      (node (ref "U1") (pin "F5") (pinfunction "IO_L55N_M3A14_3_F5") (pintype "bidirectional"))
    )
    (net (code "254") (name "unconnected-(U1D-IO_L55P_M3A13_3-PadF6)") (class "Default")
      (node (ref "U1") (pin "F6") (pinfunction "IO_L55P_M3A13_3_F6") (pintype "bidirectional"))
    )
    (net (code "255") (name "unconnected-(U1D-IO_L83N_VREF_3-PadA3)") (class "Default")
      (node (ref "U1") (pin "A3") (pinfunction "IO_L83N_VREF_3_A3") (pintype "bidirectional"))
    )
    (net (code "256") (name "unconnected-(U1D-IO_L83P_3-PadB3)") (class "Default")
      (node (ref "U1") (pin "B3") (pinfunction "IO_L83P_3_B3") (pintype "bidirectional"))
    )
    (net (code "257") (name "unconnected-(U3-PA11-USART1CTS{slash}CANRX{slash}USBDM{slash}TIM1CH4-Pad44)") (class "Default")
      (node (ref "U3") (pin "44") (pinfunction "PA11-USART1CTS/CANRX/USBDM/TIM1CH4_44") (pintype "bidirectional"))
    )
    (net (code "258") (name "unconnected-(U3-PA12-USART1RTS{slash}CANTX{slash}USBDP{slash}TIM1ETR-Pad45)") (class "Default")
      (node (ref "U3") (pin "45") (pinfunction "PA12-USART1RTS/CANTX/USBDP/TIM1ETR_45") (pintype "bidirectional"))
    )
    (net (code "259") (name "unconnected-(U3-PB2{slash}BOOT1-Pad28)") (class "Default")
      (node (ref "U3") (pin "28") (pinfunction "PB2/BOOT1_28") (pintype "bidirectional"))
    )
    (net (code "260") (name "unconnected-(U3-PB4{slash}JNTRST--TIM3CH1{slash}SPI1MISO-Pad56)") (class "Default")
      (node (ref "U3") (pin "56") (pinfunction "PB4/JNTRST--TIM3CH1/SPI1MISO_56") (pintype "bidirectional"))
    )
    (net (code "261") (name "unconnected-(U3-PB5-I2C1SMBAI-TIM3CH2{slash}SPI1MOSI-Pad57)") (class "Default")
      (node (ref "U3") (pin "57") (pinfunction "PB5-I2C1SMBAI-TIM3CH2/SPI1MOSI_57") (pintype "bidirectional"))
    )
    (net (code "262") (name "unconnected-(U3-PB6-I2C1SCL{slash}TIM4CH1-USART1TX-Pad58)") (class "Default")
      (node (ref "U3") (pin "58") (pinfunction "PB6-I2C1SCL/TIM4CH1-USART1TX_58") (pintype "bidirectional"))
    )
    (net (code "263") (name "unconnected-(U3-PB7-I2C1SDA{slash}TIM4CH2-USART1RX-Pad59)") (class "Default")
      (node (ref "U3") (pin "59") (pinfunction "PB7-I2C1SDA/TIM4CH2-USART1RX_59") (pintype "bidirectional"))
    )
    (net (code "264") (name "unconnected-(U3-PC8-TIM3CH3-Pad39)") (class "Default")
      (node (ref "U3") (pin "39") (pinfunction "PC8-TIM3CH3_39") (pintype "bidirectional"))
    )
    (net (code "265") (name "unconnected-(U3-PC9-TIM3CH4-Pad40)") (class "Default")
      (node (ref "U3") (pin "40") (pinfunction "PC9-TIM3CH4_40") (pintype "bidirectional"))
    )
    (net (code "266") (name "unconnected-(U3-PC13-TAMPER-RTC-Pad2)") (class "Default")
      (node (ref "U3") (pin "2") (pinfunction "PC13-TAMPER-RTC_2") (pintype "bidirectional"))
    )
    (net (code "267") (name "unconnected-(U3-PC14-OSC32_IN-Pad3)") (class "Default")
      (node (ref "U3") (pin "3") (pinfunction "PC14-OSC32_IN_3") (pintype "bidirectional"))
    )
    (net (code "268") (name "unconnected-(U3-PC15-OSC32_OUT-Pad4)") (class "Default")
      (node (ref "U3") (pin "4") (pinfunction "PC15-OSC32_OUT_4") (pintype "bidirectional"))
    )
    (net (code "269") (name "unconnected-(U3-PD1-OSC_OUT-CANTX-Pad6)") (class "Default")
      (node (ref "U3") (pin "6") (pinfunction "PD1-OSC_OUT-CANTX_6") (pintype "output"))
    )
    (net (code "270") (name "unconnected-(U3-PD2-TIM3ETR-Pad54)") (class "Default")
      (node (ref "U3") (pin "54") (pinfunction "PD2-TIM3ETR_54") (pintype "bidirectional"))
    )
    (net (code "271") (name "unconnected-(U7-AC8-Pad32)") (class "Default")
      (node (ref "U7") (pin "32") (pinfunction "AC8_32") (pintype "bidirectional"))
    )
    (net (code "272") (name "unconnected-(U7-AC9-Pad33)") (class "Default")
      (node (ref "U7") (pin "33") (pinfunction "AC9_33") (pintype "bidirectional"))
    )
    (net (code "273") (name "unconnected-(U7-AD2-Pad15)") (class "Default")
      (node (ref "U7") (pin "15") (pinfunction "AD2_15") (pintype "bidirectional"))
    )
    (net (code "274") (name "unconnected-(U7-AD3-Pad16)") (class "Default")
      (node (ref "U7") (pin "16") (pinfunction "AD3_16") (pintype "bidirectional"))
    )
    (net (code "275") (name "unconnected-(U7-AD4-Pad17)") (class "Default")
      (node (ref "U7") (pin "17") (pinfunction "AD4_17") (pintype "bidirectional"))
    )
    (net (code "276") (name "unconnected-(U10B-NC1-Pad22)") (class "Default")
      (node (ref "U10") (pin "22") (pinfunction "NC1_22") (pintype "bidirectional"))
    )
    (net (code "277") (name "unconnected-(U10B-TSEN-Pad28)") (class "Default")
      (node (ref "U10") (pin "28") (pinfunction "TSEN_28") (pintype "output"))
    )
    (net (code "278") (name "unconnected-(U12-NC-Pad4)") (class "Default")
      (node (ref "U12") (pin "4") (pinfunction "NC_4") (pintype "bidirectional"))
    )
  )
)
